# SchedaRobotica.net
KiCad netlist of a schematic drawn in EAGLE
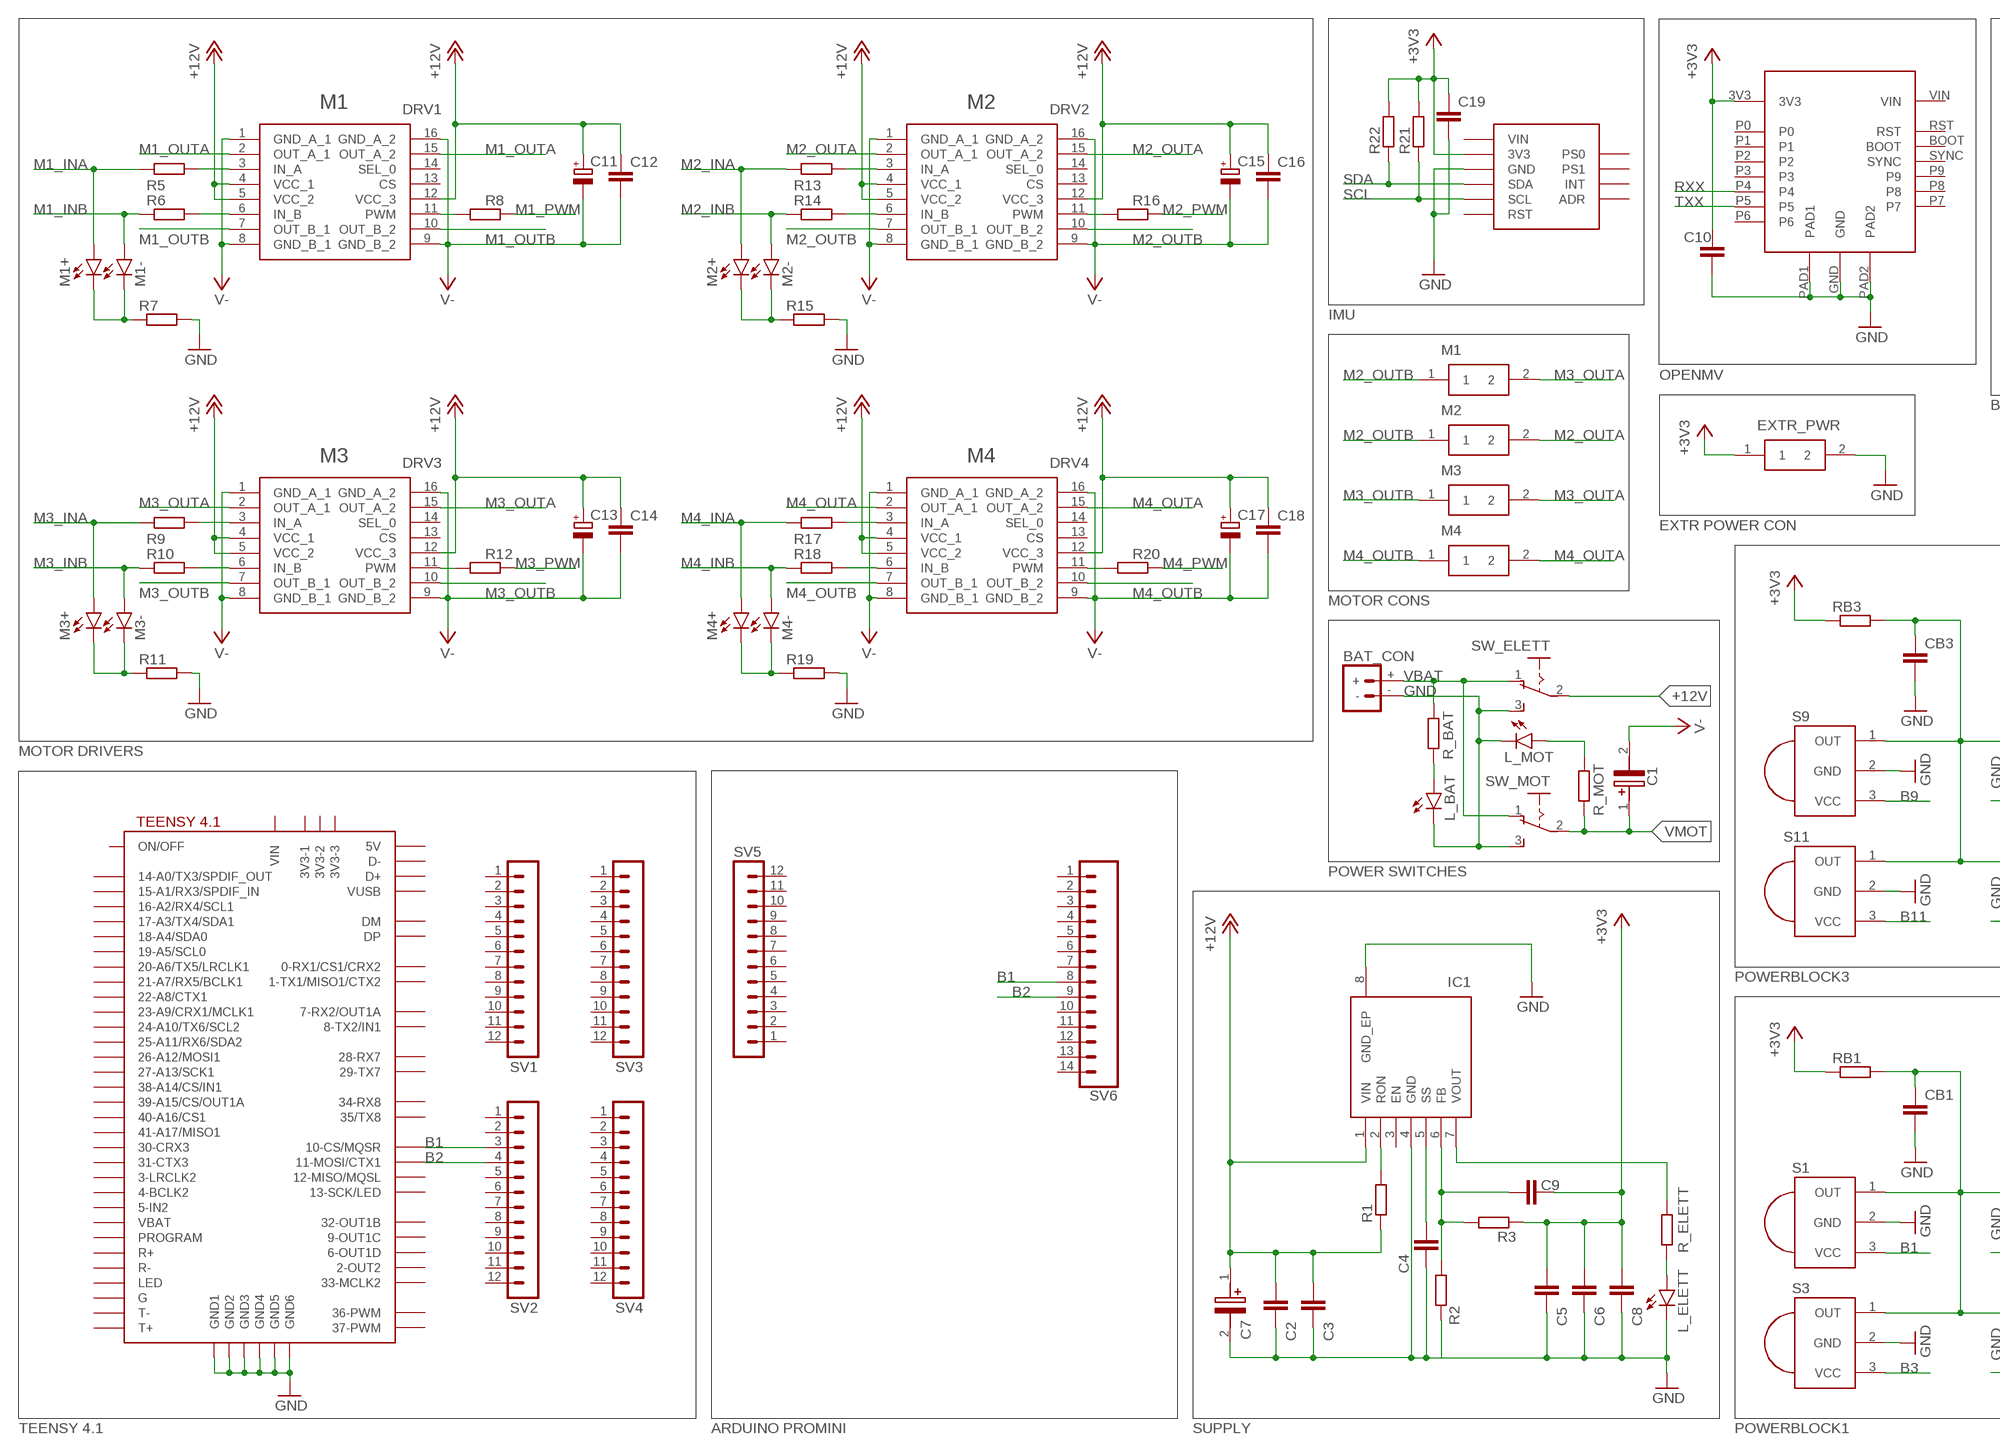
[diagram p0: schematic, sheet 1, part 1 of 2]
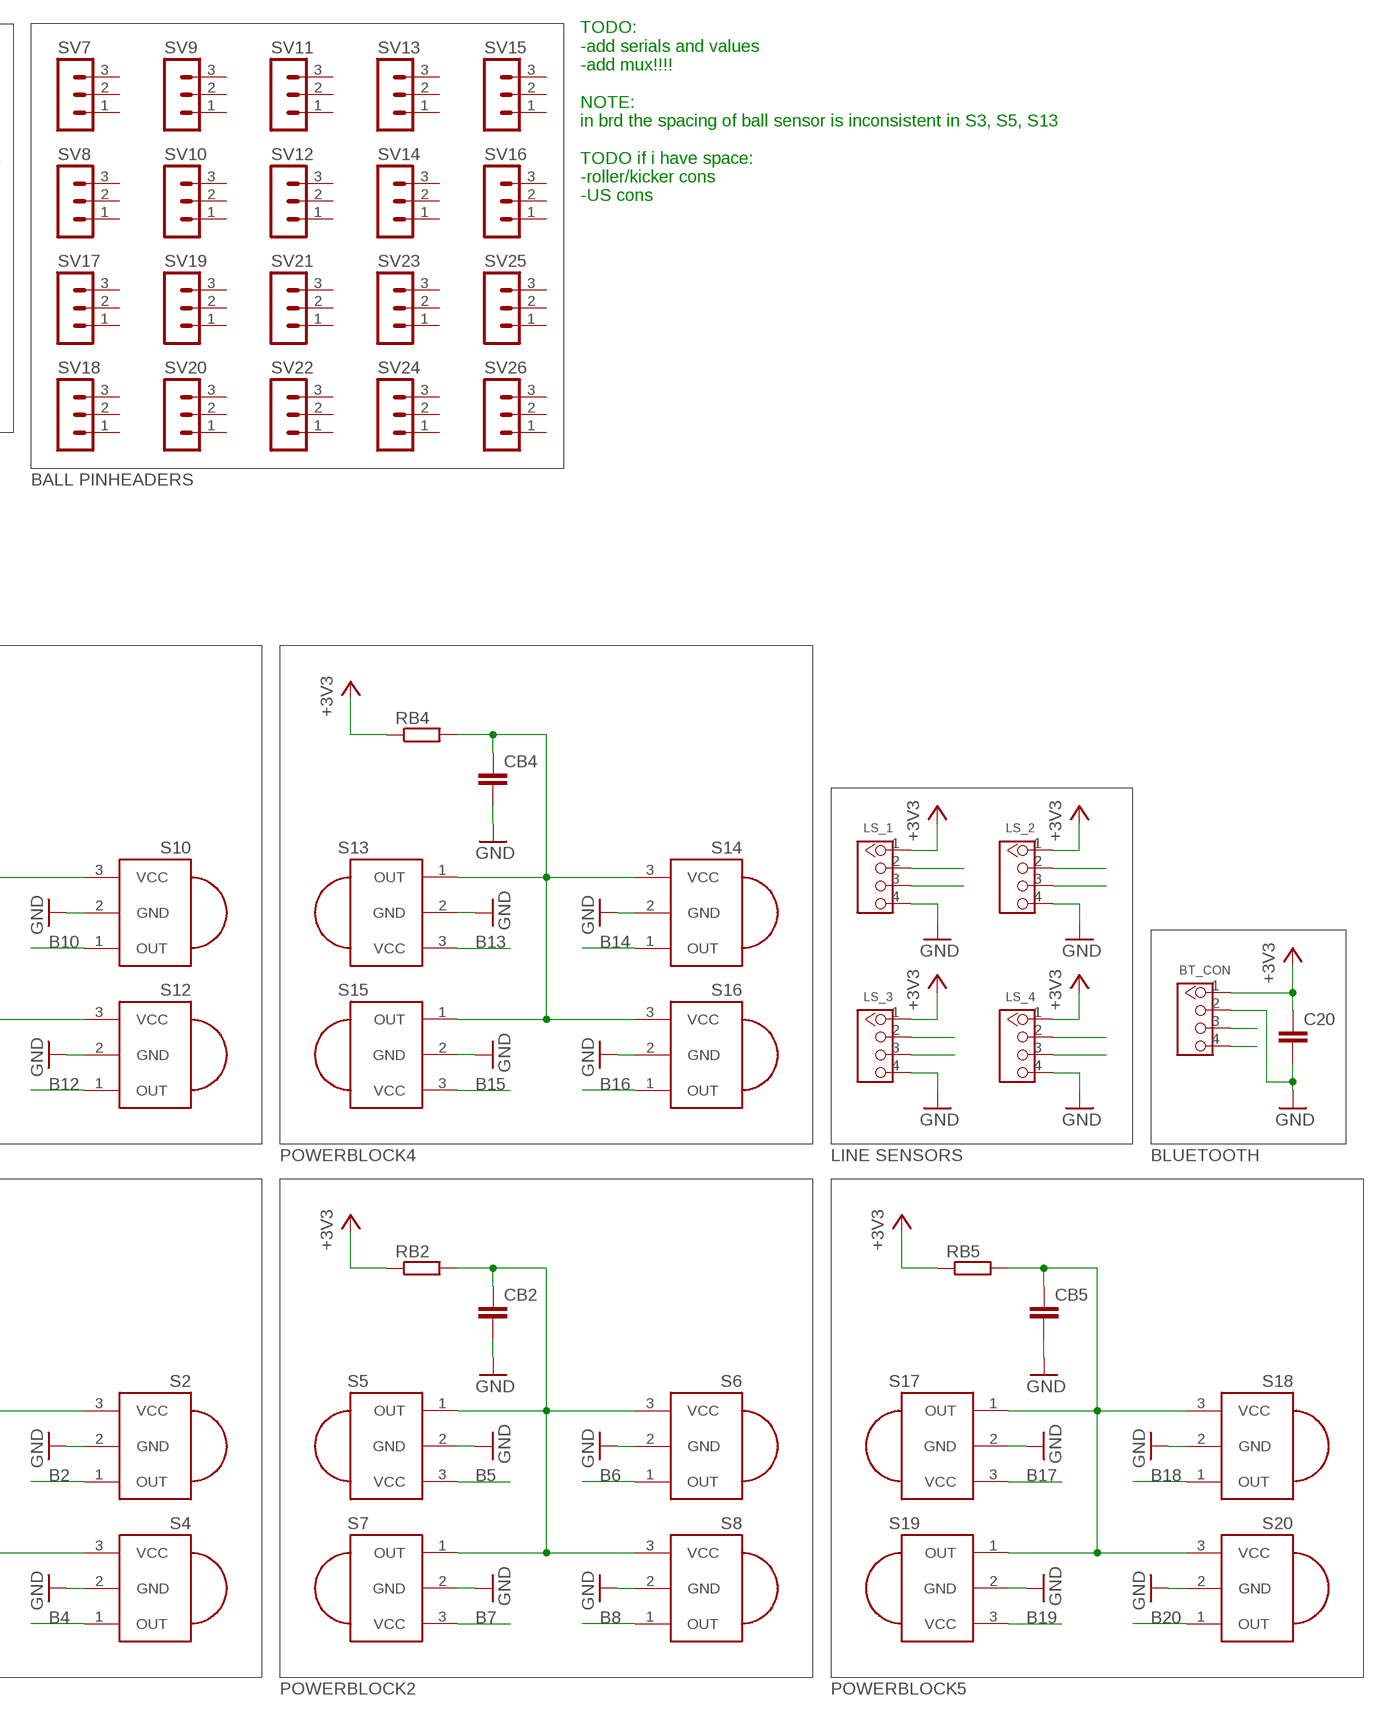
[diagram p1: schematic, sheet 1, part 2 of 2]

(export (version "E")
  (design (tool "Eeschema 10.0.6"))
  (components
    (comp (ref "BAT_CON")
      (value "BATTERY_CONN_DEANS")
      (footprint "eagle-import:DEANS")
      (libsource (lib "eagle-import") (part "BATTERY_CONN_DEANS"))
    )
    (comp (ref "BT_CON")
      (value "4P-2.0")
      (footprint "eagle-import:HW4-2.0")
      (libsource (lib "eagle-import") (part "GROVE-CONNECTOR-DIP(4P-2.0)"))
    )
    (comp (ref "C1")
      (value "EEV-FK1C152Q")
      (footprint "eagle-import:FKV(H13)")
      (fields (field (name "MOUSER_PART_NUMBER") "667-EEV-FK1C152Q"))
      (libsource (lib "eagle-import") (part "EEV-FK1C152Q"))
    )
    (comp (ref "C2")
      (value "100n")
      (footprint "eagle-import:C0805")
      (libsource (lib "eagle-import") (part "C-EUC0805"))
    )
    (comp (ref "C3")
      (value "100n")
      (footprint "eagle-import:C0805")
      (libsource (lib "eagle-import") (part "C-EUC0805"))
    )
    (comp (ref "C4")
      (value "22n")
      (footprint "eagle-import:C0805")
      (libsource (lib "eagle-import") (part "C-EUC0805"))
    )
    (comp (ref "C5")
      (value "100u")
      (footprint "eagle-import:C1206")
      (libsource (lib "eagle-import") (part "C-EUC1206"))
    )
    (comp (ref "C6")
      (value "100u")
      (footprint "eagle-import:C1206")
      (libsource (lib "eagle-import") (part "C-EUC1206"))
    )
    (comp (ref "C7")
      (value "EEV-FK1C152Q")
      (footprint "eagle-import:FKV(H13)")
      (fields (field (name "MOUSER_PART_NUMBER") "667-EEV-FK1C152Q"))
      (libsource (lib "eagle-import") (part "EEV-FK1C152Q"))
    )
    (comp (ref "C8")
      (value "100n")
      (footprint "eagle-import:C0805")
      (libsource (lib "eagle-import") (part "C-EUC0805"))
    )
    (comp (ref "C9")
      (value "22n")
      (footprint "eagle-import:C0805")
      (libsource (lib "eagle-import") (part "C-EUC0805"))
    )
    (comp (ref "C10")
      (value "100u")
      (footprint "eagle-import:C1206")
      (libsource (lib "eagle-import") (part "C-EUC1206"))
    )
    (comp (ref "C11")
      (value "CPOL-EUE")
      (footprint "eagle-import:PANASONIC_E")
      (libsource (lib "eagle-import") (part "CPOL-EUE"))
    )
    (comp (ref "C12")
      (value "C-EUC0805")
      (footprint "eagle-import:C0805")
      (libsource (lib "eagle-import") (part "C-EUC0805"))
    )
    (comp (ref "C13")
      (value "CPOL-EUE")
      (footprint "eagle-import:PANASONIC_E")
      (libsource (lib "eagle-import") (part "CPOL-EUE"))
    )
    (comp (ref "C14")
      (value "C-EUC0805")
      (footprint "eagle-import:C0805")
      (libsource (lib "eagle-import") (part "C-EUC0805"))
    )
    (comp (ref "C15")
      (value "CPOL-EUE")
      (footprint "eagle-import:PANASONIC_E")
      (libsource (lib "eagle-import") (part "CPOL-EUE"))
    )
    (comp (ref "C16")
      (value "C-EUC0805")
      (footprint "eagle-import:C0805")
      (libsource (lib "eagle-import") (part "C-EUC0805"))
    )
    (comp (ref "C17")
      (value "CPOL-EUE")
      (footprint "eagle-import:PANASONIC_E")
      (libsource (lib "eagle-import") (part "CPOL-EUE"))
    )
    (comp (ref "C18")
      (value "C-EUC0805")
      (footprint "eagle-import:C0805")
      (libsource (lib "eagle-import") (part "C-EUC0805"))
    )
    (comp (ref "C19")
      (value "1u")
      (footprint "eagle-import:C0805")
      (libsource (lib "eagle-import") (part "C-EUC0805"))
    )
    (comp (ref "C20")
      (value "1u")
      (footprint "eagle-import:C0805")
      (libsource (lib "eagle-import") (part "C-EUC0805"))
    )
    (comp (ref "CB1")
      (value "C-EUC0805")
      (footprint "eagle-import:C0805")
      (libsource (lib "eagle-import") (part "C-EUC0805"))
    )
    (comp (ref "CB2")
      (value "C-EUC0805")
      (footprint "eagle-import:C0805")
      (libsource (lib "eagle-import") (part "C-EUC0805"))
    )
    (comp (ref "CB3")
      (value "C-EUC0805")
      (footprint "eagle-import:C0805")
      (libsource (lib "eagle-import") (part "C-EUC0805"))
    )
    (comp (ref "CB4")
      (value "C-EUC0805")
      (footprint "eagle-import:C0805")
      (libsource (lib "eagle-import") (part "C-EUC0805"))
    )
    (comp (ref "CB5")
      (value "C-EUC0805")
      (footprint "eagle-import:C0805")
      (libsource (lib "eagle-import") (part "C-EUC0805"))
    )
    (comp (ref "DRV1")
      (value "VNH7070ASTR")
      (footprint "eagle-import:SOIC127P600X175-16N")
      (fields
        (field (name "MOUSER_PART_NUMBER") "511-VNH7070ASTR")
        (field (name "RS_PART_NUMBER") "1647017P")
      )
      (libsource (lib "eagle-import") (part "VNH7070ASTR"))
    )
    (comp (ref "DRV2")
      (value "VNH7070ASTR")
      (footprint "eagle-import:SOIC127P600X175-16N")
      (fields
        (field (name "MOUSER_PART_NUMBER") "511-VNH7070ASTR")
        (field (name "RS_PART_NUMBER") "1647017P")
      )
      (libsource (lib "eagle-import") (part "VNH7070ASTR"))
    )
    (comp (ref "DRV3")
      (value "VNH7070ASTR")
      (footprint "eagle-import:SOIC127P600X175-16N")
      (fields
        (field (name "MOUSER_PART_NUMBER") "511-VNH7070ASTR")
        (field (name "RS_PART_NUMBER") "1647017P")
      )
      (libsource (lib "eagle-import") (part "VNH7070ASTR"))
    )
    (comp (ref "DRV4")
      (value "VNH7070ASTR")
      (footprint "eagle-import:SOIC127P600X175-16N")
      (fields
        (field (name "MOUSER_PART_NUMBER") "511-VNH7070ASTR")
        (field (name "RS_PART_NUMBER") "1647017P")
      )
      (libsource (lib "eagle-import") (part "VNH7070ASTR"))
    )
    (comp (ref "EXTR_PWR")
      (value "43650-0201")
      (footprint "eagle-import:43650-0200")
      (fields (field (name "MOUSER_PART_NUMBER") "538-43650-0201"))
      (libsource (lib "eagle-import") (part "43650-0201"))
    )
    (comp (ref "IC1")
      (value "LMZ14202TZE-ADJ_NOPB")
      (footprint "eagle-import:NDW0007A")
      (fields
        (field (name "MANUFACTURER_PART_NUMBER") "LMZ14202TZE-ADJ/NOPB")
        (field (name "MOUSER_PART_NUMBER") "926-LM14202TZEADJNPB")
        (field (name "RS_PART_NUMBER") "7981195P")
      )
      (libsource (lib "eagle-import") (part "LMZ14202TZE-ADJ_NOPB"))
    )
    (comp (ref "LS_1")
      (value "4P-2.0")
      (footprint "eagle-import:HW4-2.0")
      (libsource (lib "eagle-import") (part "GROVE-CONNECTOR-DIP(4P-2.0)"))
    )
    (comp (ref "LS_2")
      (value "4P-2.0")
      (footprint "eagle-import:HW4-2.0")
      (libsource (lib "eagle-import") (part "GROVE-CONNECTOR-DIP(4P-2.0)"))
    )
    (comp (ref "LS_3")
      (value "4P-2.0")
      (footprint "eagle-import:HW4-2.0")
      (libsource (lib "eagle-import") (part "GROVE-CONNECTOR-DIP(4P-2.0)"))
    )
    (comp (ref "LS_4")
      (value "4P-2.0")
      (footprint "eagle-import:HW4-2.0")
      (libsource (lib "eagle-import") (part "GROVE-CONNECTOR-DIP(4P-2.0)"))
    )
    (comp (ref "L_BAT")
      (value "LEDCHIPLED_1206")
      (footprint "eagle-import:CHIPLED_1206")
      (libsource (lib "eagle-import") (part "LEDCHIPLED_1206"))
    )
    (comp (ref "L_ELETT")
      (value "LEDCHIPLED_1206")
      (footprint "eagle-import:CHIPLED_1206")
      (libsource (lib "eagle-import") (part "LEDCHIPLED_1206"))
    )
    (comp (ref "L_MOT")
      (value "LEDCHIPLED_1206")
      (footprint "eagle-import:CHIPLED_1206")
      (libsource (lib "eagle-import") (part "LEDCHIPLED_1206"))
    )
    (comp (ref "M1")
      (value "43650-0201")
      (footprint "eagle-import:43650-0200")
      (fields (field (name "MOUSER_PART_NUMBER") "538-43650-0201"))
      (libsource (lib "eagle-import") (part "43650-0201"))
    )
    (comp (ref "M1+")
      (value "LEDCHIPLED_1206")
      (footprint "eagle-import:CHIPLED_1206")
      (libsource (lib "eagle-import") (part "LEDCHIPLED_1206"))
    )
    (comp (ref "M1-")
      (value "LEDCHIPLED_1206")
      (footprint "eagle-import:CHIPLED_1206")
      (libsource (lib "eagle-import") (part "LEDCHIPLED_1206"))
    )
    (comp (ref "M2")
      (value "43650-0201")
      (footprint "eagle-import:43650-0200")
      (fields (field (name "MOUSER_PART_NUMBER") "538-43650-0201"))
      (libsource (lib "eagle-import") (part "43650-0201"))
    )
    (comp (ref "M2+")
      (value "LEDCHIPLED_1206")
      (footprint "eagle-import:CHIPLED_1206")
      (libsource (lib "eagle-import") (part "LEDCHIPLED_1206"))
    )
    (comp (ref "M2-")
      (value "LEDCHIPLED_1206")
      (footprint "eagle-import:CHIPLED_1206")
      (libsource (lib "eagle-import") (part "LEDCHIPLED_1206"))
    )
    (comp (ref "M3")
      (value "43650-0201")
      (footprint "eagle-import:43650-0200")
      (fields (field (name "MOUSER_PART_NUMBER") "538-43650-0201"))
      (libsource (lib "eagle-import") (part "43650-0201"))
    )
    (comp (ref "M3+")
      (value "LEDCHIPLED_1206")
      (footprint "eagle-import:CHIPLED_1206")
      (libsource (lib "eagle-import") (part "LEDCHIPLED_1206"))
    )
    (comp (ref "M3-")
      (value "LEDCHIPLED_1206")
      (footprint "eagle-import:CHIPLED_1206")
      (libsource (lib "eagle-import") (part "LEDCHIPLED_1206"))
    )
    (comp (ref "M4")
      (value "43650-0201")
      (footprint "eagle-import:43650-0200")
      (fields (field (name "MOUSER_PART_NUMBER") "538-43650-0201"))
      (libsource (lib "eagle-import") (part "43650-0201"))
    )
    (comp (ref "M4+")
      (value "LEDCHIPLED_1206")
      (footprint "eagle-import:CHIPLED_1206")
      (libsource (lib "eagle-import") (part "LEDCHIPLED_1206"))
    )
    (comp (ref "M4-")
      (value "LEDCHIPLED_1206")
      (footprint "eagle-import:CHIPLED_1206")
      (libsource (lib "eagle-import") (part "LEDCHIPLED_1206"))
    )
    (comp (ref "R1")
      (value "61,9k")
      (footprint "eagle-import:M0805")
      (libsource (lib "eagle-import") (part "R-EU_M0805"))
    )
    (comp (ref "R2")
      (value "1,07k")
      (footprint "eagle-import:M0805")
      (libsource (lib "eagle-import") (part "R-EU_M0805"))
    )
    (comp (ref "R3")
      (value "3,32k")
      (footprint "eagle-import:M0805")
      (libsource (lib "eagle-import") (part "R-EU_M0805"))
    )
    (comp (ref "R5")
      (value "R-EU_M0805")
      (footprint "eagle-import:M0805")
      (libsource (lib "eagle-import") (part "R-EU_M0805"))
    )
    (comp (ref "R6")
      (value "R-EU_M0805")
      (footprint "eagle-import:M0805")
      (libsource (lib "eagle-import") (part "R-EU_M0805"))
    )
    (comp (ref "R7")
      (value "R-EU_M0805")
      (footprint "eagle-import:M0805")
      (libsource (lib "eagle-import") (part "R-EU_M0805"))
    )
    (comp (ref "R8")
      (value "R-EU_M0805")
      (footprint "eagle-import:M0805")
      (libsource (lib "eagle-import") (part "R-EU_M0805"))
    )
    (comp (ref "R9")
      (value "R-EU_M0805")
      (footprint "eagle-import:M0805")
      (libsource (lib "eagle-import") (part "R-EU_M0805"))
    )
    (comp (ref "R10")
      (value "R-EU_M0805")
      (footprint "eagle-import:M0805")
      (libsource (lib "eagle-import") (part "R-EU_M0805"))
    )
    (comp (ref "R11")
      (value "R-EU_M0805")
      (footprint "eagle-import:M0805")
      (libsource (lib "eagle-import") (part "R-EU_M0805"))
    )
    (comp (ref "R12")
      (value "R-EU_M0805")
      (footprint "eagle-import:M0805")
      (libsource (lib "eagle-import") (part "R-EU_M0805"))
    )
    (comp (ref "R13")
      (value "R-EU_M0805")
      (footprint "eagle-import:M0805")
      (libsource (lib "eagle-import") (part "R-EU_M0805"))
    )
    (comp (ref "R14")
      (value "R-EU_M0805")
      (footprint "eagle-import:M0805")
      (libsource (lib "eagle-import") (part "R-EU_M0805"))
    )
    (comp (ref "R15")
      (value "R-EU_M0805")
      (footprint "eagle-import:M0805")
      (libsource (lib "eagle-import") (part "R-EU_M0805"))
    )
    (comp (ref "R16")
      (value "R-EU_M0805")
      (footprint "eagle-import:M0805")
      (libsource (lib "eagle-import") (part "R-EU_M0805"))
    )
    (comp (ref "R17")
      (value "R-EU_M0805")
      (footprint "eagle-import:M0805")
      (libsource (lib "eagle-import") (part "R-EU_M0805"))
    )
    (comp (ref "R18")
      (value "R-EU_M0805")
      (footprint "eagle-import:M0805")
      (libsource (lib "eagle-import") (part "R-EU_M0805"))
    )
    (comp (ref "R19")
      (value "R-EU_M0805")
      (footprint "eagle-import:M0805")
      (libsource (lib "eagle-import") (part "R-EU_M0805"))
    )
    (comp (ref "R20")
      (value "R-EU_M0805")
      (footprint "eagle-import:M0805")
      (libsource (lib "eagle-import") (part "R-EU_M0805"))
    )
    (comp (ref "R21")
      (value "10k")
      (footprint "eagle-import:M0805")
      (libsource (lib "eagle-import") (part "R-EU_M0805"))
    )
    (comp (ref "R22")
      (value "10k")
      (footprint "eagle-import:M0805")
      (libsource (lib "eagle-import") (part "R-EU_M0805"))
    )
    (comp (ref "RB1")
      (value "R-EU_M0805")
      (footprint "eagle-import:M0805")
      (libsource (lib "eagle-import") (part "R-EU_M0805"))
    )
    (comp (ref "RB2")
      (value "R-EU_M0805")
      (footprint "eagle-import:M0805")
      (libsource (lib "eagle-import") (part "R-EU_M0805"))
    )
    (comp (ref "RB3")
      (value "R-EU_M0805")
      (footprint "eagle-import:M0805")
      (libsource (lib "eagle-import") (part "R-EU_M0805"))
    )
    (comp (ref "RB4")
      (value "R-EU_M0805")
      (footprint "eagle-import:M0805")
      (libsource (lib "eagle-import") (part "R-EU_M0805"))
    )
    (comp (ref "RB5")
      (value "R-EU_M0805")
      (footprint "eagle-import:M0805")
      (libsource (lib "eagle-import") (part "R-EU_M0805"))
    )
    (comp (ref "R_BAT")
      (value "R-EU_M0805")
      (footprint "eagle-import:M0805")
      (libsource (lib "eagle-import") (part "R-EU_M0805"))
    )
    (comp (ref "R_ELETT")
      (value "R-EU_M0805")
      (footprint "eagle-import:M0805")
      (libsource (lib "eagle-import") (part "R-EU_M0805"))
    )
    (comp (ref "R_MOT")
      (value "R-EU_M0805")
      (footprint "eagle-import:M0805")
      (libsource (lib "eagle-import") (part "R-EU_M0805"))
    )
    (comp (ref "S1")
      (value "PNA460XM")
      (footprint "eagle-import:PNA460XM")
      (libsource (lib "eagle-import") (part "PNA460XM"))
    )
    (comp (ref "S2")
      (value "PNA460XM")
      (footprint "eagle-import:PNA460XM")
      (libsource (lib "eagle-import") (part "PNA460XM"))
    )
    (comp (ref "S3")
      (value "PNA460XM")
      (footprint "eagle-import:PNA460XM")
      (libsource (lib "eagle-import") (part "PNA460XM"))
    )
    (comp (ref "S4")
      (value "PNA460XM")
      (footprint "eagle-import:PNA460XM")
      (libsource (lib "eagle-import") (part "PNA460XM"))
    )
    (comp (ref "S5")
      (value "PNA460XM")
      (footprint "eagle-import:PNA460XM")
      (libsource (lib "eagle-import") (part "PNA460XM"))
    )
    (comp (ref "S6")
      (value "PNA460XM")
      (footprint "eagle-import:PNA460XM")
      (libsource (lib "eagle-import") (part "PNA460XM"))
    )
    (comp (ref "S7")
      (value "PNA460XM")
      (footprint "eagle-import:PNA460XM")
      (libsource (lib "eagle-import") (part "PNA460XM"))
    )
    (comp (ref "S8")
      (value "PNA460XM")
      (footprint "eagle-import:PNA460XM")
      (libsource (lib "eagle-import") (part "PNA460XM"))
    )
    (comp (ref "S9")
      (value "PNA460XM")
      (footprint "eagle-import:PNA460XM")
      (libsource (lib "eagle-import") (part "PNA460XM"))
    )
    (comp (ref "S10")
      (value "PNA460XM")
      (footprint "eagle-import:PNA460XM")
      (libsource (lib "eagle-import") (part "PNA460XM"))
    )
    (comp (ref "S11")
      (value "PNA460XM")
      (footprint "eagle-import:PNA460XM")
      (libsource (lib "eagle-import") (part "PNA460XM"))
    )
    (comp (ref "S12")
      (value "PNA460XM")
      (footprint "eagle-import:PNA460XM")
      (libsource (lib "eagle-import") (part "PNA460XM"))
    )
    (comp (ref "S13")
      (value "PNA460XM")
      (footprint "eagle-import:PNA460XM")
      (libsource (lib "eagle-import") (part "PNA460XM"))
    )
    (comp (ref "S14")
      (value "PNA460XM")
      (footprint "eagle-import:PNA460XM")
      (libsource (lib "eagle-import") (part "PNA460XM"))
    )
    (comp (ref "S15")
      (value "PNA460XM")
      (footprint "eagle-import:PNA460XM")
      (libsource (lib "eagle-import") (part "PNA460XM"))
    )
    (comp (ref "S16")
      (value "PNA460XM")
      (footprint "eagle-import:PNA460XM")
      (libsource (lib "eagle-import") (part "PNA460XM"))
    )
    (comp (ref "S17")
      (value "PNA460XM")
      (footprint "eagle-import:PNA460XM")
      (libsource (lib "eagle-import") (part "PNA460XM"))
    )
    (comp (ref "S18")
      (value "PNA460XM")
      (footprint "eagle-import:PNA460XM")
      (libsource (lib "eagle-import") (part "PNA460XM"))
    )
    (comp (ref "S19")
      (value "PNA460XM")
      (footprint "eagle-import:PNA460XM")
      (libsource (lib "eagle-import") (part "PNA460XM"))
    )
    (comp (ref "S20")
      (value "PNA460XM")
      (footprint "eagle-import:PNA460XM")
      (libsource (lib "eagle-import") (part "PNA460XM"))
    )
    (comp (ref "SV1")
      (value "MA12-1")
      (footprint "eagle-import:MA12-1")
      (libsource (lib "eagle-import") (part "MA12-1"))
    )
    (comp (ref "SV2")
      (value "MA12-1")
      (footprint "eagle-import:MA12-1")
      (libsource (lib "eagle-import") (part "MA12-1"))
    )
    (comp (ref "SV3")
      (value "MA12-1")
      (footprint "eagle-import:MA12-1")
      (libsource (lib "eagle-import") (part "MA12-1"))
    )
    (comp (ref "SV4")
      (value "MA12-1")
      (footprint "eagle-import:MA12-1")
      (libsource (lib "eagle-import") (part "MA12-1"))
    )
    (comp (ref "SV5")
      (value "MA12-1")
      (footprint "eagle-import:MA12-1")
      (libsource (lib "eagle-import") (part "MA12-1"))
    )
    (comp (ref "SV6")
      (value "CONN_14LONGPADS")
      (footprint "eagle-import:1X14-LONGPADS")
      (libsource (lib "eagle-import") (part "CONN_14LONGPADS"))
    )
    (comp (ref "SV7")
      (value "MA03-1")
      (footprint "eagle-import:MA03-1")
      (libsource (lib "eagle-import") (part "MA03-1"))
    )
    (comp (ref "SV8")
      (value "MA03-1")
      (footprint "eagle-import:MA03-1")
      (libsource (lib "eagle-import") (part "MA03-1"))
    )
    (comp (ref "SV9")
      (value "MA03-1")
      (footprint "eagle-import:MA03-1")
      (libsource (lib "eagle-import") (part "MA03-1"))
    )
    (comp (ref "SV10")
      (value "MA03-1")
      (footprint "eagle-import:MA03-1")
      (libsource (lib "eagle-import") (part "MA03-1"))
    )
    (comp (ref "SV11")
      (value "MA03-1")
      (footprint "eagle-import:MA03-1")
      (libsource (lib "eagle-import") (part "MA03-1"))
    )
    (comp (ref "SV12")
      (value "MA03-1")
      (footprint "eagle-import:MA03-1")
      (libsource (lib "eagle-import") (part "MA03-1"))
    )
    (comp (ref "SV13")
      (value "MA03-1")
      (footprint "eagle-import:MA03-1")
      (libsource (lib "eagle-import") (part "MA03-1"))
    )
    (comp (ref "SV14")
      (value "MA03-1")
      (footprint "eagle-import:MA03-1")
      (libsource (lib "eagle-import") (part "MA03-1"))
    )
    (comp (ref "SV15")
      (value "MA03-1")
      (footprint "eagle-import:MA03-1")
      (libsource (lib "eagle-import") (part "MA03-1"))
    )
    (comp (ref "SV16")
      (value "MA03-1")
      (footprint "eagle-import:MA03-1")
      (libsource (lib "eagle-import") (part "MA03-1"))
    )
    (comp (ref "SV17")
      (value "MA03-1")
      (footprint "eagle-import:MA03-1")
      (libsource (lib "eagle-import") (part "MA03-1"))
    )
    (comp (ref "SV18")
      (value "MA03-1")
      (footprint "eagle-import:MA03-1")
      (libsource (lib "eagle-import") (part "MA03-1"))
    )
    (comp (ref "SV19")
      (value "MA03-1")
      (footprint "eagle-import:MA03-1")
      (libsource (lib "eagle-import") (part "MA03-1"))
    )
    (comp (ref "SV20")
      (value "MA03-1")
      (footprint "eagle-import:MA03-1")
      (libsource (lib "eagle-import") (part "MA03-1"))
    )
    (comp (ref "SV21")
      (value "MA03-1")
      (footprint "eagle-import:MA03-1")
      (libsource (lib "eagle-import") (part "MA03-1"))
    )
    (comp (ref "SV22")
      (value "MA03-1")
      (footprint "eagle-import:MA03-1")
      (libsource (lib "eagle-import") (part "MA03-1"))
    )
    (comp (ref "SV23")
      (value "MA03-1")
      (footprint "eagle-import:MA03-1")
      (libsource (lib "eagle-import") (part "MA03-1"))
    )
    (comp (ref "SV24")
      (value "MA03-1")
      (footprint "eagle-import:MA03-1")
      (libsource (lib "eagle-import") (part "MA03-1"))
    )
    (comp (ref "SV25")
      (value "MA03-1")
      (footprint "eagle-import:MA03-1")
      (libsource (lib "eagle-import") (part "MA03-1"))
    )
    (comp (ref "SV26")
      (value "MA03-1")
      (footprint "eagle-import:MA03-1")
      (libsource (lib "eagle-import") (part "MA03-1"))
    )
    (comp (ref "SW_ELETT")
      (value "255SB")
      (footprint "eagle-import:255SB")
      (libsource (lib "eagle-import") (part "255SB"))
    )
    (comp (ref "SW_MOT")
      (value "255SB")
      (footprint "eagle-import:255SB")
      (libsource (lib "eagle-import") (part "255SB"))
    )
    (comp (ref "U$1")
      (value "TEENSY41")
      (footprint "eagle-import:TEENSY41")
      (libsource (lib "eagle-import") (part "TEENSY41"))
    )
    (comp (ref "U$2")
      (value "OPENMV_H7")
      (footprint "eagle-import:OPENMV_H7")
      (libsource (lib "eagle-import") (part "OPENMV_H7"))
    )
    (comp (ref "U$3")
      (value "BNO055_BNO055")
      (footprint "eagle-import:BNO055_BNO055")
      (libsource (lib "eagle-import") (part "BNO055_BNO055"))
    )
  )
  (nets
    (net (code "1") (name "+3V3") (class "Default")
      (node (ref "BT_CON") (pin "1") (pinfunction "1_1") (pintype "bidirectional"))
      (node (ref "C10") (pin "1") (pinfunction "1_1") (pintype "passive"))
      (node (ref "C19") (pin "1") (pinfunction "1_1") (pintype "passive"))
      (node (ref "C20") (pin "1") (pinfunction "1_1") (pintype "passive"))
      (node (ref "C5") (pin "1") (pinfunction "1_1") (pintype "passive"))
      (node (ref "C6") (pin "1") (pinfunction "1_1") (pintype "passive"))
      (node (ref "C8") (pin "1") (pinfunction "1_1") (pintype "passive"))
      (node (ref "C9") (pin "2") (pinfunction "2_2") (pintype "passive"))
      (node (ref "EXTR_PWR") (pin "1") (pinfunction "1_1") (pintype "bidirectional"))
      (node (ref "LS_1") (pin "1") (pinfunction "1_1") (pintype "bidirectional"))
      (node (ref "LS_2") (pin "1") (pinfunction "1_1") (pintype "bidirectional"))
      (node (ref "LS_3") (pin "1") (pinfunction "1_1") (pintype "bidirectional"))
      (node (ref "LS_4") (pin "1") (pinfunction "1_1") (pintype "bidirectional"))
      (node (ref "R21") (pin "2") (pinfunction "2_2") (pintype "passive"))
      (node (ref "R22") (pin "2") (pinfunction "2_2") (pintype "passive"))
      (node (ref "R3") (pin "1") (pinfunction "1_1") (pintype "passive"))
      (node (ref "RB1") (pin "1") (pinfunction "1_1") (pintype "passive"))
      (node (ref "RB2") (pin "1") (pinfunction "1_1") (pintype "passive"))
      (node (ref "RB3") (pin "1") (pinfunction "1_1") (pintype "passive"))
      (node (ref "RB4") (pin "1") (pinfunction "1_1") (pintype "passive"))
      (node (ref "RB5") (pin "1") (pinfunction "1_1") (pintype "passive"))
      (node (ref "U$2") (pin "3V3") (pinfunction "3V3_3V3") (pintype "bidirectional"))
      (node (ref "U$3") (pin "3V3") (pinfunction "3V3_3V3") (pintype "bidirectional"))
    )
    (net (code "2") (name "+12V") (class "Default")
      (node (ref "C11") (pin "+") (pinfunction "+_+") (pintype "passive"))
      (node (ref "C12") (pin "1") (pinfunction "1_1") (pintype "passive"))
      (node (ref "C13") (pin "+") (pinfunction "+_+") (pintype "passive"))
      (node (ref "C14") (pin "1") (pinfunction "1_1") (pintype "passive"))
      (node (ref "C15") (pin "+") (pinfunction "+_+") (pintype "passive"))
      (node (ref "C16") (pin "1") (pinfunction "1_1") (pintype "passive"))
      (node (ref "C17") (pin "+") (pinfunction "+_+") (pintype "passive"))
      (node (ref "C18") (pin "1") (pinfunction "1_1") (pintype "passive"))
      (node (ref "C2") (pin "1") (pinfunction "1_1") (pintype "passive"))
      (node (ref "C3") (pin "1") (pinfunction "1_1") (pintype "passive"))
      (node (ref "C7") (pin "1") (pinfunction "+_1") (pintype "bidirectional"))
      (node (ref "DRV1") (pin "12") (pinfunction "VCC_3_12") (pintype "bidirectional"))
      (node (ref "DRV1") (pin "4") (pinfunction "VCC_1_4") (pintype "bidirectional"))
      (node (ref "DRV1") (pin "5") (pinfunction "VCC_2_5") (pintype "bidirectional"))
      (node (ref "DRV2") (pin "12") (pinfunction "VCC_3_12") (pintype "bidirectional"))
      (node (ref "DRV2") (pin "4") (pinfunction "VCC_1_4") (pintype "bidirectional"))
      (node (ref "DRV2") (pin "5") (pinfunction "VCC_2_5") (pintype "bidirectional"))
      (node (ref "DRV3") (pin "12") (pinfunction "VCC_3_12") (pintype "bidirectional"))
      (node (ref "DRV3") (pin "4") (pinfunction "VCC_1_4") (pintype "bidirectional"))
      (node (ref "DRV3") (pin "5") (pinfunction "VCC_2_5") (pintype "bidirectional"))
      (node (ref "DRV4") (pin "12") (pinfunction "VCC_3_12") (pintype "bidirectional"))
      (node (ref "DRV4") (pin "4") (pinfunction "VCC_1_4") (pintype "bidirectional"))
      (node (ref "DRV4") (pin "5") (pinfunction "VCC_2_5") (pintype "bidirectional"))
      (node (ref "IC1") (pin "1") (pinfunction "VIN_1") (pintype "input"))
      (node (ref "R1") (pin "1") (pinfunction "1_1") (pintype "passive"))
      (node (ref "SW_ELETT") (pin "2") (pinfunction "P_2") (pintype "passive"))
    )
    (net (code "3") (name "/B1") (class "Default")
      (node (ref "S1") (pin "3") (pinfunction "VCC_3") (pintype "power_in"))
      (node (ref "SV2") (pin "3") (pinfunction "3_3") (pintype "passive"))
      (node (ref "SV6") (pin "8") (pinfunction "8_8") (pintype "passive"))
      (node (ref "U$1") (pin "10-CS\\MQSR") (pinfunction "10-CS/MQSR_10-CS\\MQSR") (pintype "bidirectional"))
    )
    (net (code "4") (name "/B2") (class "Default")
      (node (ref "S2") (pin "1") (pinfunction "OUT_1") (pintype "output"))
      (node (ref "SV2") (pin "4") (pinfunction "4_4") (pintype "passive"))
      (node (ref "SV6") (pin "9") (pinfunction "9_9") (pintype "passive"))
      (node (ref "U$1") (pin "11-MOSI/CTX1") (pinfunction "11-MOSI/CTX1_11-MOSI/CTX1") (pintype "bidirectional"))
    )
    (net (code "5") (name "/B3") (class "Default")
      (node (ref "S3") (pin "3") (pinfunction "VCC_3") (pintype "power_in"))
    )
    (net (code "6") (name "/B4") (class "Default")
      (node (ref "S4") (pin "1") (pinfunction "OUT_1") (pintype "output"))
    )
    (net (code "7") (name "/B5") (class "Default")
      (node (ref "S5") (pin "3") (pinfunction "VCC_3") (pintype "power_in"))
    )
    (net (code "8") (name "/B6") (class "Default")
      (node (ref "S6") (pin "1") (pinfunction "OUT_1") (pintype "output"))
    )
    (net (code "9") (name "/B7") (class "Default")
      (node (ref "S7") (pin "3") (pinfunction "VCC_3") (pintype "power_in"))
    )
    (net (code "10") (name "/B8") (class "Default")
      (node (ref "S8") (pin "1") (pinfunction "OUT_1") (pintype "output"))
    )
    (net (code "11") (name "/B9") (class "Default")
      (node (ref "S9") (pin "3") (pinfunction "VCC_3") (pintype "power_in"))
    )
    (net (code "12") (name "/B10") (class "Default")
      (node (ref "S10") (pin "1") (pinfunction "OUT_1") (pintype "output"))
    )
    (net (code "13") (name "/B11") (class "Default")
      (node (ref "S11") (pin "3") (pinfunction "VCC_3") (pintype "power_in"))
    )
    (net (code "14") (name "/B12") (class "Default")
      (node (ref "S12") (pin "1") (pinfunction "OUT_1") (pintype "output"))
    )
    (net (code "15") (name "/B13") (class "Default")
      (node (ref "S13") (pin "3") (pinfunction "VCC_3") (pintype "power_in"))
    )
    (net (code "16") (name "/B14") (class "Default")
      (node (ref "S14") (pin "1") (pinfunction "OUT_1") (pintype "output"))
    )
    (net (code "17") (name "/B15") (class "Default")
      (node (ref "S15") (pin "3") (pinfunction "VCC_3") (pintype "power_in"))
    )
    (net (code "18") (name "/B16") (class "Default")
      (node (ref "S16") (pin "1") (pinfunction "OUT_1") (pintype "output"))
    )
    (net (code "19") (name "/B17") (class "Default")
      (node (ref "S17") (pin "3") (pinfunction "VCC_3") (pintype "power_in"))
    )
    (net (code "20") (name "/B18") (class "Default")
      (node (ref "S18") (pin "1") (pinfunction "OUT_1") (pintype "output"))
    )
    (net (code "21") (name "/B19") (class "Default")
      (node (ref "S19") (pin "3") (pinfunction "VCC_3") (pintype "power_in"))
    )
    (net (code "22") (name "/B20") (class "Default")
      (node (ref "S20") (pin "1") (pinfunction "OUT_1") (pintype "output"))
    )
    (net (code "23") (name "/M1_INA") (class "Default")
      (node (ref "M1+") (pin "A") (pinfunction "A_A") (pintype "passive"))
      (node (ref "R5") (pin "1") (pinfunction "1_1") (pintype "passive"))
    )
    (net (code "24") (name "/M1_INB") (class "Default")
      (node (ref "M1-") (pin "A") (pinfunction "A_A") (pintype "passive"))
      (node (ref "R6") (pin "1") (pinfunction "1_1") (pintype "passive"))
    )
    (net (code "25") (name "/M1_OUTA") (class "Default")
      (node (ref "DRV1") (pin "15") (pinfunction "OUT_A_2_15") (pintype "bidirectional"))
      (node (ref "DRV1") (pin "2") (pinfunction "OUT_A_1_2") (pintype "bidirectional"))
    )
    (net (code "26") (name "/M1_OUTB") (class "Default")
      (node (ref "DRV1") (pin "10") (pinfunction "OUT_B_2_10") (pintype "bidirectional"))
      (node (ref "DRV1") (pin "7") (pinfunction "OUT_B_1_7") (pintype "bidirectional"))
    )
    (net (code "27") (name "/M1_PWM") (class "Default")
      (node (ref "R8") (pin "2") (pinfunction "2_2") (pintype "passive"))
    )
    (net (code "28") (name "/M2_INA") (class "Default")
      (node (ref "M2+") (pin "A") (pinfunction "A_A") (pintype "passive"))
      (node (ref "R13") (pin "1") (pinfunction "1_1") (pintype "passive"))
    )
    (net (code "29") (name "/M2_INB") (class "Default")
      (node (ref "M2-") (pin "A") (pinfunction "A_A") (pintype "passive"))
      (node (ref "R14") (pin "1") (pinfunction "1_1") (pintype "passive"))
    )
    (net (code "30") (name "/M2_OUTA") (class "Default")
      (node (ref "DRV2") (pin "15") (pinfunction "OUT_A_2_15") (pintype "bidirectional"))
      (node (ref "DRV2") (pin "2") (pinfunction "OUT_A_1_2") (pintype "bidirectional"))
      (node (ref "M2") (pin "2") (pinfunction "2_2") (pintype "bidirectional"))
    )
    (net (code "31") (name "/M2_OUTB") (class "Default")
      (node (ref "DRV2") (pin "10") (pinfunction "OUT_B_2_10") (pintype "bidirectional"))
      (node (ref "DRV2") (pin "7") (pinfunction "OUT_B_1_7") (pintype "bidirectional"))
      (node (ref "M1") (pin "1") (pinfunction "1_1") (pintype "bidirectional"))
      (node (ref "M2") (pin "1") (pinfunction "1_1") (pintype "bidirectional"))
    )
    (net (code "32") (name "/M2_PWM") (class "Default")
      (node (ref "R16") (pin "2") (pinfunction "2_2") (pintype "passive"))
    )
    (net (code "33") (name "/M3_INA") (class "Default")
      (node (ref "M3+") (pin "A") (pinfunction "A_A") (pintype "passive"))
      (node (ref "R9") (pin "1") (pinfunction "1_1") (pintype "passive"))
    )
    (net (code "34") (name "/M3_INB") (class "Default")
      (node (ref "M3-") (pin "A") (pinfunction "A_A") (pintype "passive"))
      (node (ref "R10") (pin "1") (pinfunction "1_1") (pintype "passive"))
    )
    (net (code "35") (name "/M3_OUTA") (class "Default")
      (node (ref "DRV3") (pin "15") (pinfunction "OUT_A_2_15") (pintype "bidirectional"))
      (node (ref "DRV3") (pin "2") (pinfunction "OUT_A_1_2") (pintype "bidirectional"))
      (node (ref "M1") (pin "2") (pinfunction "2_2") (pintype "bidirectional"))
      (node (ref "M3") (pin "2") (pinfunction "2_2") (pintype "bidirectional"))
    )
    (net (code "36") (name "/M3_OUTB") (class "Default")
      (node (ref "DRV3") (pin "10") (pinfunction "OUT_B_2_10") (pintype "bidirectional"))
      (node (ref "DRV3") (pin "7") (pinfunction "OUT_B_1_7") (pintype "bidirectional"))
      (node (ref "M3") (pin "1") (pinfunction "1_1") (pintype "bidirectional"))
    )
    (net (code "37") (name "/M3_PWM") (class "Default")
      (node (ref "R12") (pin "2") (pinfunction "2_2") (pintype "passive"))
    )
    (net (code "38") (name "/M4_INA") (class "Default")
      (node (ref "M4+") (pin "A") (pinfunction "A_A") (pintype "passive"))
      (node (ref "R17") (pin "1") (pinfunction "1_1") (pintype "passive"))
    )
    (net (code "39") (name "/M4_INB") (class "Default")
      (node (ref "M4-") (pin "A") (pinfunction "A_A") (pintype "passive"))
      (node (ref "R18") (pin "1") (pinfunction "1_1") (pintype "passive"))
    )
    (net (code "40") (name "/M4_OUTA") (class "Default")
      (node (ref "DRV4") (pin "15") (pinfunction "OUT_A_2_15") (pintype "bidirectional"))
      (node (ref "DRV4") (pin "2") (pinfunction "OUT_A_1_2") (pintype "bidirectional"))
      (node (ref "M4") (pin "2") (pinfunction "2_2") (pintype "bidirectional"))
    )
    (net (code "41") (name "/M4_OUTB") (class "Default")
      (node (ref "DRV4") (pin "10") (pinfunction "OUT_B_2_10") (pintype "bidirectional"))
      (node (ref "DRV4") (pin "7") (pinfunction "OUT_B_1_7") (pintype "bidirectional"))
      (node (ref "M4") (pin "1") (pinfunction "1_1") (pintype "bidirectional"))
    )
    (net (code "42") (name "/M4_PWM") (class "Default")
      (node (ref "R20") (pin "2") (pinfunction "2_2") (pintype "passive"))
    )
    (net (code "43") (name "/RXX") (class "Default")
      (node (ref "U$2") (pin "P4") (pinfunction "P4_P4") (pintype "bidirectional"))
    )
    (net (code "44") (name "/SCL") (class "Default")
      (node (ref "R21") (pin "1") (pinfunction "1_1") (pintype "passive"))
      (node (ref "U$3") (pin "SCL") (pinfunction "SCL_SCL") (pintype "bidirectional"))
    )
    (net (code "45") (name "/SDA") (class "Default")
      (node (ref "R22") (pin "1") (pinfunction "1_1") (pintype "passive"))
      (node (ref "U$3") (pin "SDA") (pinfunction "SDA_SDA") (pintype "bidirectional"))
    )
    (net (code "46") (name "/TXX") (class "Default")
      (node (ref "U$2") (pin "P5") (pinfunction "P5_P5") (pintype "bidirectional"))
    )
    (net (code "47") (name "/VBAT") (class "Default")
      (node (ref "BAT_CON") (pin "+") (pinfunction "+_+") (pintype "passive"))
      (node (ref "R_BAT") (pin "1") (pinfunction "1_1") (pintype "passive"))
      (node (ref "SW_ELETT") (pin "1") (pinfunction "O_1") (pintype "passive"))
      (node (ref "SW_MOT") (pin "1") (pinfunction "O_1") (pintype "passive"))
    )
    (net (code "48") (name "GND") (class "Default")
      (node (ref "BAT_CON") (pin "-") (pinfunction "-_-") (pintype "passive"))
      (node (ref "BT_CON") (pin "2") (pinfunction "2_2") (pintype "bidirectional"))
      (node (ref "C10") (pin "2") (pinfunction "2_2") (pintype "passive"))
      (node (ref "C19") (pin "2") (pinfunction "2_2") (pintype "passive"))
      (node (ref "C2") (pin "2") (pinfunction "2_2") (pintype "passive"))
      (node (ref "C20") (pin "2") (pinfunction "2_2") (pintype "passive"))
      (node (ref "C3") (pin "2") (pinfunction "2_2") (pintype "passive"))
      (node (ref "C4") (pin "2") (pinfunction "2_2") (pintype "passive"))
      (node (ref "C5") (pin "2") (pinfunction "2_2") (pintype "passive"))
      (node (ref "C6") (pin "2") (pinfunction "2_2") (pintype "passive"))
      (node (ref "C7") (pin "2") (pinfunction "-_2") (pintype "bidirectional"))
      (node (ref "C8") (pin "2") (pinfunction "2_2") (pintype "passive"))
      (node (ref "CB1") (pin "2") (pinfunction "2_2") (pintype "passive"))
      (node (ref "CB2") (pin "2") (pinfunction "2_2") (pintype "passive"))
      (node (ref "CB3") (pin "2") (pinfunction "2_2") (pintype "passive"))
      (node (ref "CB4") (pin "2") (pinfunction "2_2") (pintype "passive"))
      (node (ref "CB5") (pin "2") (pinfunction "2_2") (pintype "passive"))
      (node (ref "EXTR_PWR") (pin "2") (pinfunction "2_2") (pintype "bidirectional"))
      (node (ref "IC1") (pin "4") (pinfunction "GND_4") (pintype "power_in"))
      (node (ref "IC1") (pin "8") (pinfunction "GND_EP_8") (pintype "power_in"))
      (node (ref "LS_1") (pin "4") (pinfunction "4_4") (pintype "bidirectional"))
      (node (ref "LS_2") (pin "4") (pinfunction "4_4") (pintype "bidirectional"))
      (node (ref "LS_3") (pin "4") (pinfunction "4_4") (pintype "bidirectional"))
      (node (ref "LS_4") (pin "4") (pinfunction "4_4") (pintype "bidirectional"))
      (node (ref "L_BAT") (pin "C") (pinfunction "C_C") (pintype "passive"))
      (node (ref "L_ELETT") (pin "C") (pinfunction "C_C") (pintype "passive"))
      (node (ref "L_MOT") (pin "C") (pinfunction "C_C") (pintype "passive"))
      (node (ref "R11") (pin "2") (pinfunction "2_2") (pintype "passive"))
      (node (ref "R15") (pin "2") (pinfunction "2_2") (pintype "passive"))
      (node (ref "R19") (pin "2") (pinfunction "2_2") (pintype "passive"))
      (node (ref "R2") (pin "1") (pinfunction "1_1") (pintype "passive"))
      (node (ref "R7") (pin "2") (pinfunction "2_2") (pintype "passive"))
      (node (ref "S1") (pin "2") (pinfunction "GND_2") (pintype "power_in"))
      (node (ref "S10") (pin "2") (pinfunction "GND_2") (pintype "power_in"))
      (node (ref "S11") (pin "2") (pinfunction "GND_2") (pintype "power_in"))
      (node (ref "S12") (pin "2") (pinfunction "GND_2") (pintype "power_in"))
      (node (ref "S13") (pin "2") (pinfunction "GND_2") (pintype "power_in"))
      (node (ref "S14") (pin "2") (pinfunction "GND_2") (pintype "power_in"))
      (node (ref "S15") (pin "2") (pinfunction "GND_2") (pintype "power_in"))
      (node (ref "S16") (pin "2") (pinfunction "GND_2") (pintype "power_in"))
      (node (ref "S17") (pin "2") (pinfunction "GND_2") (pintype "power_in"))
      (node (ref "S18") (pin "2") (pinfunction "GND_2") (pintype "power_in"))
      (node (ref "S19") (pin "2") (pinfunction "GND_2") (pintype "power_in"))
      (node (ref "S2") (pin "2") (pinfunction "GND_2") (pintype "power_in"))
      (node (ref "S20") (pin "2") (pinfunction "GND_2") (pintype "power_in"))
      (node (ref "S3") (pin "2") (pinfunction "GND_2") (pintype "power_in"))
      (node (ref "S4") (pin "2") (pinfunction "GND_2") (pintype "power_in"))
      (node (ref "S5") (pin "2") (pinfunction "GND_2") (pintype "power_in"))
      (node (ref "S6") (pin "2") (pinfunction "GND_2") (pintype "power_in"))
      (node (ref "S7") (pin "2") (pinfunction "GND_2") (pintype "power_in"))
      (node (ref "S8") (pin "2") (pinfunction "GND_2") (pintype "power_in"))
      (node (ref "S9") (pin "2") (pinfunction "GND_2") (pintype "power_in"))
      (node (ref "SW_ELETT") (pin "3") (pinfunction "S_3") (pintype "passive"))
      (node (ref "SW_MOT") (pin "3") (pinfunction "S_3") (pintype "passive"))
      (node (ref "U$1") (pin "GND1") (pinfunction "GND1_GND1") (pintype "bidirectional"))
      (node (ref "U$1") (pin "GND2") (pinfunction "GND2_GND2") (pintype "bidirectional"))
      (node (ref "U$1") (pin "GND3") (pinfunction "GND3_GND3") (pintype "bidirectional"))
      (node (ref "U$1") (pin "GND4") (pinfunction "GND4_GND4") (pintype "bidirectional"))
      (node (ref "U$1") (pin "GND5") (pinfunction "GND5_GND5") (pintype "bidirectional"))
      (node (ref "U$1") (pin "GND6") (pinfunction "GND6_GND6") (pintype "bidirectional"))
      (node (ref "U$2") (pin "GND") (pinfunction "GND_GND") (pintype "bidirectional"))
      (node (ref "U$2") (pin "PAD1") (pinfunction "PAD1_PAD1") (pintype "bidirectional"))
      (node (ref "U$2") (pin "PAD2") (pinfunction "PAD2_PAD2") (pintype "bidirectional"))
      (node (ref "U$3") (pin "GND") (pinfunction "GND_GND") (pintype "bidirectional"))
    )
    (net (code "49") (name "Net-(DRV1-IN_A)") (class "Default")
      (node (ref "DRV1") (pin "3") (pinfunction "IN_A_3") (pintype "bidirectional"))
      (node (ref "R5") (pin "2") (pinfunction "2_2") (pintype "passive"))
    )
    (net (code "50") (name "Net-(DRV1-IN_B)") (class "Default")
      (node (ref "DRV1") (pin "6") (pinfunction "IN_B_6") (pintype "bidirectional"))
      (node (ref "R6") (pin "2") (pinfunction "2_2") (pintype "passive"))
    )
    (net (code "51") (name "Net-(DRV1-PWM)") (class "Default")
      (node (ref "DRV1") (pin "11") (pinfunction "PWM_11") (pintype "bidirectional"))
      (node (ref "R8") (pin "1") (pinfunction "1_1") (pintype "passive"))
    )
    (net (code "52") (name "Net-(DRV2-IN_A)") (class "Default")
      (node (ref "DRV2") (pin "3") (pinfunction "IN_A_3") (pintype "bidirectional"))
      (node (ref "R13") (pin "2") (pinfunction "2_2") (pintype "passive"))
    )
    (net (code "53") (name "Net-(DRV2-IN_B)") (class "Default")
      (node (ref "DRV2") (pin "6") (pinfunction "IN_B_6") (pintype "bidirectional"))
      (node (ref "R14") (pin "2") (pinfunction "2_2") (pintype "passive"))
    )
    (net (code "54") (name "Net-(DRV2-PWM)") (class "Default")
      (node (ref "DRV2") (pin "11") (pinfunction "PWM_11") (pintype "bidirectional"))
      (node (ref "R16") (pin "1") (pinfunction "1_1") (pintype "passive"))
    )
    (net (code "55") (name "Net-(DRV3-IN_A)") (class "Default")
      (node (ref "DRV3") (pin "3") (pinfunction "IN_A_3") (pintype "bidirectional"))
      (node (ref "R9") (pin "2") (pinfunction "2_2") (pintype "passive"))
    )
    (net (code "56") (name "Net-(DRV3-IN_B)") (class "Default")
      (node (ref "DRV3") (pin "6") (pinfunction "IN_B_6") (pintype "bidirectional"))
      (node (ref "R10") (pin "2") (pinfunction "2_2") (pintype "passive"))
    )
    (net (code "57") (name "Net-(DRV3-PWM)") (class "Default")
      (node (ref "DRV3") (pin "11") (pinfunction "PWM_11") (pintype "bidirectional"))
      (node (ref "R12") (pin "1") (pinfunction "1_1") (pintype "passive"))
    )
    (net (code "58") (name "Net-(DRV4-IN_A)") (class "Default")
      (node (ref "DRV4") (pin "3") (pinfunction "IN_A_3") (pintype "bidirectional"))
      (node (ref "R17") (pin "2") (pinfunction "2_2") (pintype "passive"))
    )
    (net (code "59") (name "Net-(DRV4-IN_B)") (class "Default")
      (node (ref "DRV4") (pin "6") (pinfunction "IN_B_6") (pintype "bidirectional"))
      (node (ref "R18") (pin "2") (pinfunction "2_2") (pintype "passive"))
    )
    (net (code "60") (name "Net-(DRV4-PWM)") (class "Default")
      (node (ref "DRV4") (pin "11") (pinfunction "PWM_11") (pintype "bidirectional"))
      (node (ref "R20") (pin "1") (pinfunction "1_1") (pintype "passive"))
    )
    (net (code "61") (name "Net-(IC1-FB)") (class "Default")
      (node (ref "C9") (pin "1") (pinfunction "1_1") (pintype "passive"))
      (node (ref "IC1") (pin "6") (pinfunction "FB_6") (pintype "bidirectional"))
      (node (ref "R2") (pin "2") (pinfunction "2_2") (pintype "passive"))
      (node (ref "R3") (pin "2") (pinfunction "2_2") (pintype "passive"))
    )
    (net (code "62") (name "Net-(IC1-RON)") (class "Default")
      (node (ref "IC1") (pin "2") (pinfunction "RON_2") (pintype "bidirectional"))
      (node (ref "R1") (pin "2") (pinfunction "2_2") (pintype "passive"))
    )
    (net (code "63") (name "Net-(IC1-SS)") (class "Default")
      (node (ref "C4") (pin "1") (pinfunction "1_1") (pintype "passive"))
      (node (ref "IC1") (pin "5") (pinfunction "SS_5") (pintype "bidirectional"))
    )
    (net (code "64") (name "Net-(IC1-VOUT)") (class "Default")
      (node (ref "IC1") (pin "7") (pinfunction "VOUT_7") (pintype "output"))
      (node (ref "R_ELETT") (pin "2") (pinfunction "2_2") (pintype "passive"))
    )
    (net (code "65") (name "Net-(L_BAT-PadA)") (class "Default")
      (node (ref "L_BAT") (pin "A") (pinfunction "A_A") (pintype "passive"))
      (node (ref "R_BAT") (pin "2") (pinfunction "2_2") (pintype "passive"))
    )
    (net (code "66") (name "Net-(L_ELETT-PadA)") (class "Default")
      (node (ref "L_ELETT") (pin "A") (pinfunction "A_A") (pintype "passive"))
      (node (ref "R_ELETT") (pin "1") (pinfunction "1_1") (pintype "passive"))
    )
    (net (code "67") (name "Net-(L_MOT-PadA)") (class "Default")
      (node (ref "L_MOT") (pin "A") (pinfunction "A_A") (pintype "passive"))
      (node (ref "R_MOT") (pin "1") (pinfunction "1_1") (pintype "passive"))
    )
    (net (code "68") (name "Net-(M1+-PadC)") (class "Default")
      (node (ref "M1+") (pin "C") (pinfunction "C_C") (pintype "passive"))
      (node (ref "M1-") (pin "C") (pinfunction "C_C") (pintype "passive"))
      (node (ref "R7") (pin "1") (pinfunction "1_1") (pintype "passive"))
    )
    (net (code "69") (name "Net-(M2+-PadC)") (class "Default")
      (node (ref "M2+") (pin "C") (pinfunction "C_C") (pintype "passive"))
      (node (ref "M2-") (pin "C") (pinfunction "C_C") (pintype "passive"))
      (node (ref "R15") (pin "1") (pinfunction "1_1") (pintype "passive"))
    )
    (net (code "70") (name "Net-(M3+-PadC)") (class "Default")
      (node (ref "M3+") (pin "C") (pinfunction "C_C") (pintype "passive"))
      (node (ref "M3-") (pin "C") (pinfunction "C_C") (pintype "passive"))
      (node (ref "R11") (pin "1") (pinfunction "1_1") (pintype "passive"))
    )
    (net (code "71") (name "Net-(M4+-PadC)") (class "Default")
      (node (ref "M4+") (pin "C") (pinfunction "C_C") (pintype "passive"))
      (node (ref "M4-") (pin "C") (pinfunction "C_C") (pintype "passive"))
      (node (ref "R19") (pin "1") (pinfunction "1_1") (pintype "passive"))
    )
    (net (code "72") (name "Net-(S1-OUT)") (class "Default")
      (node (ref "CB1") (pin "1") (pinfunction "1_1") (pintype "passive"))
      (node (ref "RB1") (pin "2") (pinfunction "2_2") (pintype "passive"))
      (node (ref "S1") (pin "1") (pinfunction "OUT_1") (pintype "output"))
      (node (ref "S2") (pin "3") (pinfunction "VCC_3") (pintype "power_in"))
      (node (ref "S3") (pin "1") (pinfunction "OUT_1") (pintype "output"))
      (node (ref "S4") (pin "3") (pinfunction "VCC_3") (pintype "power_in"))
    )
    (net (code "73") (name "Net-(S5-OUT)") (class "Default")
      (node (ref "CB2") (pin "1") (pinfunction "1_1") (pintype "passive"))
      (node (ref "RB2") (pin "2") (pinfunction "2_2") (pintype "passive"))
      (node (ref "S5") (pin "1") (pinfunction "OUT_1") (pintype "output"))
      (node (ref "S6") (pin "3") (pinfunction "VCC_3") (pintype "power_in"))
      (node (ref "S7") (pin "1") (pinfunction "OUT_1") (pintype "output"))
      (node (ref "S8") (pin "3") (pinfunction "VCC_3") (pintype "power_in"))
    )
    (net (code "74") (name "Net-(S10-VCC)") (class "Default")
      (node (ref "CB3") (pin "1") (pinfunction "1_1") (pintype "passive"))
      (node (ref "RB3") (pin "2") (pinfunction "2_2") (pintype "passive"))
      (node (ref "S10") (pin "3") (pinfunction "VCC_3") (pintype "power_in"))
      (node (ref "S11") (pin "1") (pinfunction "OUT_1") (pintype "output"))
      (node (ref "S12") (pin "3") (pinfunction "VCC_3") (pintype "power_in"))
      (node (ref "S9") (pin "1") (pinfunction "OUT_1") (pintype "output"))
    )
    (net (code "75") (name "Net-(S13-OUT)") (class "Default")
      (node (ref "CB4") (pin "1") (pinfunction "1_1") (pintype "passive"))
      (node (ref "RB4") (pin "2") (pinfunction "2_2") (pintype "passive"))
      (node (ref "S13") (pin "1") (pinfunction "OUT_1") (pintype "output"))
      (node (ref "S14") (pin "3") (pinfunction "VCC_3") (pintype "power_in"))
      (node (ref "S15") (pin "1") (pinfunction "OUT_1") (pintype "output"))
      (node (ref "S16") (pin "3") (pinfunction "VCC_3") (pintype "power_in"))
    )
    (net (code "76") (name "Net-(S17-OUT)") (class "Default")
      (node (ref "CB5") (pin "1") (pinfunction "1_1") (pintype "passive"))
      (node (ref "RB5") (pin "2") (pinfunction "2_2") (pintype "passive"))
      (node (ref "S17") (pin "1") (pinfunction "OUT_1") (pintype "output"))
      (node (ref "S18") (pin "3") (pinfunction "VCC_3") (pintype "power_in"))
      (node (ref "S19") (pin "1") (pinfunction "OUT_1") (pintype "output"))
      (node (ref "S20") (pin "3") (pinfunction "VCC_3") (pintype "power_in"))
    )
    (net (code "77") (name "V-") (class "Default")
      (node (ref "C1") (pin "2") (pinfunction "-_2") (pintype "bidirectional"))
      (node (ref "C11") (pin "-") (pinfunction "-_-") (pintype "passive"))
      (node (ref "C12") (pin "2") (pinfunction "2_2") (pintype "passive"))
      (node (ref "C13") (pin "-") (pinfunction "-_-") (pintype "passive"))
      (node (ref "C14") (pin "2") (pinfunction "2_2") (pintype "passive"))
      (node (ref "C15") (pin "-") (pinfunction "-_-") (pintype "passive"))
      (node (ref "C16") (pin "2") (pinfunction "2_2") (pintype "passive"))
      (node (ref "C17") (pin "-") (pinfunction "-_-") (pintype "passive"))
      (node (ref "C18") (pin "2") (pinfunction "2_2") (pintype "passive"))
      (node (ref "DRV1") (pin "1") (pinfunction "GND_A_1_1") (pintype "bidirectional"))
      (node (ref "DRV1") (pin "16") (pinfunction "GND_A_2_16") (pintype "bidirectional"))
      (node (ref "DRV1") (pin "8") (pinfunction "GND_B_1_8") (pintype "bidirectional"))
      (node (ref "DRV1") (pin "9") (pinfunction "GND_B_2_9") (pintype "bidirectional"))
      (node (ref "DRV2") (pin "1") (pinfunction "GND_A_1_1") (pintype "bidirectional"))
      (node (ref "DRV2") (pin "16") (pinfunction "GND_A_2_16") (pintype "bidirectional"))
      (node (ref "DRV2") (pin "8") (pinfunction "GND_B_1_8") (pintype "bidirectional"))
      (node (ref "DRV2") (pin "9") (pinfunction "GND_B_2_9") (pintype "bidirectional"))
      (node (ref "DRV3") (pin "1") (pinfunction "GND_A_1_1") (pintype "bidirectional"))
      (node (ref "DRV3") (pin "16") (pinfunction "GND_A_2_16") (pintype "bidirectional"))
      (node (ref "DRV3") (pin "8") (pinfunction "GND_B_1_8") (pintype "bidirectional"))
      (node (ref "DRV3") (pin "9") (pinfunction "GND_B_2_9") (pintype "bidirectional"))
      (node (ref "DRV4") (pin "1") (pinfunction "GND_A_1_1") (pintype "bidirectional"))
      (node (ref "DRV4") (pin "16") (pinfunction "GND_A_2_16") (pintype "bidirectional"))
      (node (ref "DRV4") (pin "8") (pinfunction "GND_B_1_8") (pintype "bidirectional"))
      (node (ref "DRV4") (pin "9") (pinfunction "GND_B_2_9") (pintype "bidirectional"))
    )
    (net (code "78") (name "VMOT") (class "Default")
      (node (ref "C1") (pin "1") (pinfunction "+_1") (pintype "bidirectional"))
      (node (ref "R_MOT") (pin "2") (pinfunction "2_2") (pintype "passive"))
      (node (ref "SW_MOT") (pin "2") (pinfunction "P_2") (pintype "passive"))
    )
    (net (code "79") (name "unconnected-(BT_CON-Pad3)") (class "Default")
      (node (ref "BT_CON") (pin "3") (pinfunction "3_3") (pintype "bidirectional"))
    )
    (net (code "80") (name "unconnected-(BT_CON-Pad4)") (class "Default")
      (node (ref "BT_CON") (pin "4") (pinfunction "4_4") (pintype "bidirectional"))
    )
    (net (code "81") (name "unconnected-(DRV1-CS-Pad13)") (class "Default")
      (node (ref "DRV1") (pin "13") (pinfunction "CS_13") (pintype "bidirectional"))
    )
    (net (code "82") (name "unconnected-(DRV1-SEL_0-Pad14)") (class "Default")
      (node (ref "DRV1") (pin "14") (pinfunction "SEL_0_14") (pintype "bidirectional"))
    )
    (net (code "83") (name "unconnected-(DRV2-CS-Pad13)") (class "Default")
      (node (ref "DRV2") (pin "13") (pinfunction "CS_13") (pintype "bidirectional"))
    )
    (net (code "84") (name "unconnected-(DRV2-SEL_0-Pad14)") (class "Default")
      (node (ref "DRV2") (pin "14") (pinfunction "SEL_0_14") (pintype "bidirectional"))
    )
    (net (code "85") (name "unconnected-(DRV3-CS-Pad13)") (class "Default")
      (node (ref "DRV3") (pin "13") (pinfunction "CS_13") (pintype "bidirectional"))
    )
    (net (code "86") (name "unconnected-(DRV3-SEL_0-Pad14)") (class "Default")
      (node (ref "DRV3") (pin "14") (pinfunction "SEL_0_14") (pintype "bidirectional"))
    )
    (net (code "87") (name "unconnected-(DRV4-CS-Pad13)") (class "Default")
      (node (ref "DRV4") (pin "13") (pinfunction "CS_13") (pintype "bidirectional"))
    )
    (net (code "88") (name "unconnected-(DRV4-SEL_0-Pad14)") (class "Default")
      (node (ref "DRV4") (pin "14") (pinfunction "SEL_0_14") (pintype "bidirectional"))
    )
    (net (code "89") (name "unconnected-(IC1-EN-Pad3)") (class "Default")
      (node (ref "IC1") (pin "3") (pinfunction "EN_3") (pintype "bidirectional"))
    )
    (net (code "90") (name "unconnected-(LS_1-Pad2)") (class "Default")
      (node (ref "LS_1") (pin "2") (pinfunction "2_2") (pintype "bidirectional"))
    )
    (net (code "91") (name "unconnected-(LS_1-Pad3)") (class "Default")
      (node (ref "LS_1") (pin "3") (pinfunction "3_3") (pintype "bidirectional"))
    )
    (net (code "92") (name "unconnected-(LS_2-Pad2)") (class "Default")
      (node (ref "LS_2") (pin "2") (pinfunction "2_2") (pintype "bidirectional"))
    )
    (net (code "93") (name "unconnected-(LS_2-Pad3)") (class "Default")
      (node (ref "LS_2") (pin "3") (pinfunction "3_3") (pintype "bidirectional"))
    )
    (net (code "94") (name "unconnected-(LS_3-Pad2)") (class "Default")
      (node (ref "LS_3") (pin "2") (pinfunction "2_2") (pintype "bidirectional"))
    )
    (net (code "95") (name "unconnected-(LS_3-Pad3)") (class "Default")
      (node (ref "LS_3") (pin "3") (pinfunction "3_3") (pintype "bidirectional"))
    )
    (net (code "96") (name "unconnected-(LS_4-Pad2)") (class "Default")
      (node (ref "LS_4") (pin "2") (pinfunction "2_2") (pintype "bidirectional"))
    )
    (net (code "97") (name "unconnected-(LS_4-Pad3)") (class "Default")
      (node (ref "LS_4") (pin "3") (pinfunction "3_3") (pintype "bidirectional"))
    )
    (net (code "98") (name "unconnected-(SV1-Pad1)") (class "Default")
      (node (ref "SV1") (pin "1") (pinfunction "1_1") (pintype "passive"))
    )
    (net (code "99") (name "unconnected-(SV1-Pad2)") (class "Default")
      (node (ref "SV1") (pin "2") (pinfunction "2_2") (pintype "passive"))
    )
    (net (code "100") (name "unconnected-(SV1-Pad3)") (class "Default")
      (node (ref "SV1") (pin "3") (pinfunction "3_3") (pintype "passive"))
    )
    (net (code "101") (name "unconnected-(SV1-Pad4)") (class "Default")
      (node (ref "SV1") (pin "4") (pinfunction "4_4") (pintype "passive"))
    )
    (net (code "102") (name "unconnected-(SV1-Pad5)") (class "Default")
      (node (ref "SV1") (pin "5") (pinfunction "5_5") (pintype "passive"))
    )
    (net (code "103") (name "unconnected-(SV1-Pad6)") (class "Default")
      (node (ref "SV1") (pin "6") (pinfunction "6_6") (pintype "passive"))
    )
    (net (code "104") (name "unconnected-(SV1-Pad7)") (class "Default")
      (node (ref "SV1") (pin "7") (pinfunction "7_7") (pintype "passive"))
    )
    (net (code "105") (name "unconnected-(SV1-Pad8)") (class "Default")
      (node (ref "SV1") (pin "8") (pinfunction "8_8") (pintype "passive"))
    )
    (net (code "106") (name "unconnected-(SV1-Pad9)") (class "Default")
      (node (ref "SV1") (pin "9") (pinfunction "9_9") (pintype "passive"))
    )
    (net (code "107") (name "unconnected-(SV1-Pad10)") (class "Default")
      (node (ref "SV1") (pin "10") (pinfunction "10_10") (pintype "passive"))
    )
    (net (code "108") (name "unconnected-(SV1-Pad11)") (class "Default")
      (node (ref "SV1") (pin "11") (pinfunction "11_11") (pintype "passive"))
    )
    (net (code "109") (name "unconnected-(SV1-Pad12)") (class "Default")
      (node (ref "SV1") (pin "12") (pinfunction "12_12") (pintype "passive"))
    )
    (net (code "110") (name "unconnected-(SV2-Pad1)") (class "Default")
      (node (ref "SV2") (pin "1") (pinfunction "1_1") (pintype "passive"))
    )
    (net (code "111") (name "unconnected-(SV2-Pad2)") (class "Default")
      (node (ref "SV2") (pin "2") (pinfunction "2_2") (pintype "passive"))
    )
    (net (code "112") (name "unconnected-(SV2-Pad5)") (class "Default")
      (node (ref "SV2") (pin "5") (pinfunction "5_5") (pintype "passive"))
    )
    (net (code "113") (name "unconnected-(SV2-Pad6)") (class "Default")
      (node (ref "SV2") (pin "6") (pinfunction "6_6") (pintype "passive"))
    )
    (net (code "114") (name "unconnected-(SV2-Pad7)") (class "Default")
      (node (ref "SV2") (pin "7") (pinfunction "7_7") (pintype "passive"))
    )
    (net (code "115") (name "unconnected-(SV2-Pad8)") (class "Default")
      (node (ref "SV2") (pin "8") (pinfunction "8_8") (pintype "passive"))
    )
    (net (code "116") (name "unconnected-(SV2-Pad9)") (class "Default")
      (node (ref "SV2") (pin "9") (pinfunction "9_9") (pintype "passive"))
    )
    (net (code "117") (name "unconnected-(SV2-Pad10)") (class "Default")
      (node (ref "SV2") (pin "10") (pinfunction "10_10") (pintype "passive"))
    )
    (net (code "118") (name "unconnected-(SV2-Pad11)") (class "Default")
      (node (ref "SV2") (pin "11") (pinfunction "11_11") (pintype "passive"))
    )
    (net (code "119") (name "unconnected-(SV2-Pad12)") (class "Default")
      (node (ref "SV2") (pin "12") (pinfunction "12_12") (pintype "passive"))
    )
    (net (code "120") (name "unconnected-(SV3-Pad1)") (class "Default")
      (node (ref "SV3") (pin "1") (pinfunction "1_1") (pintype "passive"))
    )
    (net (code "121") (name "unconnected-(SV3-Pad2)") (class "Default")
      (node (ref "SV3") (pin "2") (pinfunction "2_2") (pintype "passive"))
    )
    (net (code "122") (name "unconnected-(SV3-Pad3)") (class "Default")
      (node (ref "SV3") (pin "3") (pinfunction "3_3") (pintype "passive"))
    )
    (net (code "123") (name "unconnected-(SV3-Pad4)") (class "Default")
      (node (ref "SV3") (pin "4") (pinfunction "4_4") (pintype "passive"))
    )
    (net (code "124") (name "unconnected-(SV3-Pad5)") (class "Default")
      (node (ref "SV3") (pin "5") (pinfunction "5_5") (pintype "passive"))
    )
    (net (code "125") (name "unconnected-(SV3-Pad6)") (class "Default")
      (node (ref "SV3") (pin "6") (pinfunction "6_6") (pintype "passive"))
    )
    (net (code "126") (name "unconnected-(SV3-Pad7)") (class "Default")
      (node (ref "SV3") (pin "7") (pinfunction "7_7") (pintype "passive"))
    )
    (net (code "127") (name "unconnected-(SV3-Pad8)") (class "Default")
      (node (ref "SV3") (pin "8") (pinfunction "8_8") (pintype "passive"))
    )
    (net (code "128") (name "unconnected-(SV3-Pad9)") (class "Default")
      (node (ref "SV3") (pin "9") (pinfunction "9_9") (pintype "passive"))
    )
    (net (code "129") (name "unconnected-(SV3-Pad10)") (class "Default")
      (node (ref "SV3") (pin "10") (pinfunction "10_10") (pintype "passive"))
    )
    (net (code "130") (name "unconnected-(SV3-Pad11)") (class "Default")
      (node (ref "SV3") (pin "11") (pinfunction "11_11") (pintype "passive"))
    )
    (net (code "131") (name "unconnected-(SV3-Pad12)") (class "Default")
      (node (ref "SV3") (pin "12") (pinfunction "12_12") (pintype "passive"))
    )
    (net (code "132") (name "unconnected-(SV4-Pad1)") (class "Default")
      (node (ref "SV4") (pin "1") (pinfunction "1_1") (pintype "passive"))
    )
    (net (code "133") (name "unconnected-(SV4-Pad2)") (class "Default")
      (node (ref "SV4") (pin "2") (pinfunction "2_2") (pintype "passive"))
    )
    (net (code "134") (name "unconnected-(SV4-Pad3)") (class "Default")
      (node (ref "SV4") (pin "3") (pinfunction "3_3") (pintype "passive"))
    )
    (net (code "135") (name "unconnected-(SV4-Pad4)") (class "Default")
      (node (ref "SV4") (pin "4") (pinfunction "4_4") (pintype "passive"))
    )
    (net (code "136") (name "unconnected-(SV4-Pad5)") (class "Default")
      (node (ref "SV4") (pin "5") (pinfunction "5_5") (pintype "passive"))
    )
    (net (code "137") (name "unconnected-(SV4-Pad6)") (class "Default")
      (node (ref "SV4") (pin "6") (pinfunction "6_6") (pintype "passive"))
    )
    (net (code "138") (name "unconnected-(SV4-Pad7)") (class "Default")
      (node (ref "SV4") (pin "7") (pinfunction "7_7") (pintype "passive"))
    )
    (net (code "139") (name "unconnected-(SV4-Pad8)") (class "Default")
      (node (ref "SV4") (pin "8") (pinfunction "8_8") (pintype "passive"))
    )
    (net (code "140") (name "unconnected-(SV4-Pad9)") (class "Default")
      (node (ref "SV4") (pin "9") (pinfunction "9_9") (pintype "passive"))
    )
    (net (code "141") (name "unconnected-(SV4-Pad10)") (class "Default")
      (node (ref "SV4") (pin "10") (pinfunction "10_10") (pintype "passive"))
    )
    (net (code "142") (name "unconnected-(SV4-Pad11)") (class "Default")
      (node (ref "SV4") (pin "11") (pinfunction "11_11") (pintype "passive"))
    )
    (net (code "143") (name "unconnected-(SV4-Pad12)") (class "Default")
      (node (ref "SV4") (pin "12") (pinfunction "12_12") (pintype "passive"))
    )
    (net (code "144") (name "unconnected-(SV5-Pad1)") (class "Default")
      (node (ref "SV5") (pin "1") (pinfunction "1_1") (pintype "passive"))
    )
    (net (code "145") (name "unconnected-(SV5-Pad2)") (class "Default")
      (node (ref "SV5") (pin "2") (pinfunction "2_2") (pintype "passive"))
    )
    (net (code "146") (name "unconnected-(SV5-Pad3)") (class "Default")
      (node (ref "SV5") (pin "3") (pinfunction "3_3") (pintype "passive"))
    )
    (net (code "147") (name "unconnected-(SV5-Pad4)") (class "Default")
      (node (ref "SV5") (pin "4") (pinfunction "4_4") (pintype "passive"))
    )
    (net (code "148") (name "unconnected-(SV5-Pad5)") (class "Default")
      (node (ref "SV5") (pin "5") (pinfunction "5_5") (pintype "passive"))
    )
    (net (code "149") (name "unconnected-(SV5-Pad6)") (class "Default")
      (node (ref "SV5") (pin "6") (pinfunction "6_6") (pintype "passive"))
    )
    (net (code "150") (name "unconnected-(SV5-Pad7)") (class "Default")
      (node (ref "SV5") (pin "7") (pinfunction "7_7") (pintype "passive"))
    )
    (net (code "151") (name "unconnected-(SV5-Pad8)") (class "Default")
      (node (ref "SV5") (pin "8") (pinfunction "8_8") (pintype "passive"))
    )
    (net (code "152") (name "unconnected-(SV5-Pad9)") (class "Default")
      (node (ref "SV5") (pin "9") (pinfunction "9_9") (pintype "passive"))
    )
    (net (code "153") (name "unconnected-(SV5-Pad10)") (class "Default")
      (node (ref "SV5") (pin "10") (pinfunction "10_10") (pintype "passive"))
    )
    (net (code "154") (name "unconnected-(SV5-Pad11)") (class "Default")
      (node (ref "SV5") (pin "11") (pinfunction "11_11") (pintype "passive"))
    )
    (net (code "155") (name "unconnected-(SV5-Pad12)") (class "Default")
      (node (ref "SV5") (pin "12") (pinfunction "12_12") (pintype "passive"))
    )
    (net (code "156") (name "unconnected-(SV6-Pad1)") (class "Default")
      (node (ref "SV6") (pin "1") (pinfunction "1_1") (pintype "passive"))
    )
    (net (code "157") (name "unconnected-(SV6-Pad2)") (class "Default")
      (node (ref "SV6") (pin "2") (pinfunction "2_2") (pintype "passive"))
    )
    (net (code "158") (name "unconnected-(SV6-Pad3)") (class "Default")
      (node (ref "SV6") (pin "3") (pinfunction "3_3") (pintype "passive"))
    )
    (net (code "159") (name "unconnected-(SV6-Pad4)") (class "Default")
      (node (ref "SV6") (pin "4") (pinfunction "4_4") (pintype "passive"))
    )
    (net (code "160") (name "unconnected-(SV6-Pad5)") (class "Default")
      (node (ref "SV6") (pin "5") (pinfunction "5_5") (pintype "passive"))
    )
    (net (code "161") (name "unconnected-(SV6-Pad6)") (class "Default")
      (node (ref "SV6") (pin "6") (pinfunction "6_6") (pintype "passive"))
    )
    (net (code "162") (name "unconnected-(SV6-Pad7)") (class "Default")
      (node (ref "SV6") (pin "7") (pinfunction "7_7") (pintype "passive"))
    )
    (net (code "163") (name "unconnected-(SV6-Pad10)") (class "Default")
      (node (ref "SV6") (pin "10") (pinfunction "10_10") (pintype "passive"))
    )
    (net (code "164") (name "unconnected-(SV6-Pad11)") (class "Default")
      (node (ref "SV6") (pin "11") (pinfunction "11_11") (pintype "passive"))
    )
    (net (code "165") (name "unconnected-(SV6-Pad12)") (class "Default")
      (node (ref "SV6") (pin "12") (pinfunction "12_12") (pintype "passive"))
    )
    (net (code "166") (name "unconnected-(SV6-Pad13)") (class "Default")
      (node (ref "SV6") (pin "13") (pinfunction "13_13") (pintype "passive"))
    )
    (net (code "167") (name "unconnected-(SV6-Pad14)") (class "Default")
      (node (ref "SV6") (pin "14") (pinfunction "14_14") (pintype "passive"))
    )
    (net (code "168") (name "unconnected-(SV7-Pad1)") (class "Default")
      (node (ref "SV7") (pin "1") (pinfunction "1_1") (pintype "passive"))
    )
    (net (code "169") (name "unconnected-(SV7-Pad2)") (class "Default")
      (node (ref "SV7") (pin "2") (pinfunction "2_2") (pintype "passive"))
    )
    (net (code "170") (name "unconnected-(SV7-Pad3)") (class "Default")
      (node (ref "SV7") (pin "3") (pinfunction "3_3") (pintype "passive"))
    )
    (net (code "171") (name "unconnected-(SV8-Pad1)") (class "Default")
      (node (ref "SV8") (pin "1") (pinfunction "1_1") (pintype "passive"))
    )
    (net (code "172") (name "unconnected-(SV8-Pad2)") (class "Default")
      (node (ref "SV8") (pin "2") (pinfunction "2_2") (pintype "passive"))
    )
    (net (code "173") (name "unconnected-(SV8-Pad3)") (class "Default")
      (node (ref "SV8") (pin "3") (pinfunction "3_3") (pintype "passive"))
    )
    (net (code "174") (name "unconnected-(SV9-Pad1)") (class "Default")
      (node (ref "SV9") (pin "1") (pinfunction "1_1") (pintype "passive"))
    )
    (net (code "175") (name "unconnected-(SV9-Pad2)") (class "Default")
      (node (ref "SV9") (pin "2") (pinfunction "2_2") (pintype "passive"))
    )
    (net (code "176") (name "unconnected-(SV9-Pad3)") (class "Default")
      (node (ref "SV9") (pin "3") (pinfunction "3_3") (pintype "passive"))
    )
    (net (code "177") (name "unconnected-(SV10-Pad1)") (class "Default")
      (node (ref "SV10") (pin "1") (pinfunction "1_1") (pintype "passive"))
    )
    (net (code "178") (name "unconnected-(SV10-Pad2)") (class "Default")
      (node (ref "SV10") (pin "2") (pinfunction "2_2") (pintype "passive"))
    )
    (net (code "179") (name "unconnected-(SV10-Pad3)") (class "Default")
      (node (ref "SV10") (pin "3") (pinfunction "3_3") (pintype "passive"))
    )
    (net (code "180") (name "unconnected-(SV11-Pad1)") (class "Default")
      (node (ref "SV11") (pin "1") (pinfunction "1_1") (pintype "passive"))
    )
    (net (code "181") (name "unconnected-(SV11-Pad2)") (class "Default")
      (node (ref "SV11") (pin "2") (pinfunction "2_2") (pintype "passive"))
    )
    (net (code "182") (name "unconnected-(SV11-Pad3)") (class "Default")
      (node (ref "SV11") (pin "3") (pinfunction "3_3") (pintype "passive"))
    )
    (net (code "183") (name "unconnected-(SV12-Pad1)") (class "Default")
      (node (ref "SV12") (pin "1") (pinfunction "1_1") (pintype "passive"))
    )
    (net (code "184") (name "unconnected-(SV12-Pad2)") (class "Default")
      (node (ref "SV12") (pin "2") (pinfunction "2_2") (pintype "passive"))
    )
    (net (code "185") (name "unconnected-(SV12-Pad3)") (class "Default")
      (node (ref "SV12") (pin "3") (pinfunction "3_3") (pintype "passive"))
    )
    (net (code "186") (name "unconnected-(SV13-Pad1)") (class "Default")
      (node (ref "SV13") (pin "1") (pinfunction "1_1") (pintype "passive"))
    )
    (net (code "187") (name "unconnected-(SV13-Pad2)") (class "Default")
      (node (ref "SV13") (pin "2") (pinfunction "2_2") (pintype "passive"))
    )
    (net (code "188") (name "unconnected-(SV13-Pad3)") (class "Default")
      (node (ref "SV13") (pin "3") (pinfunction "3_3") (pintype "passive"))
    )
    (net (code "189") (name "unconnected-(SV14-Pad1)") (class "Default")
      (node (ref "SV14") (pin "1") (pinfunction "1_1") (pintype "passive"))
    )
    (net (code "190") (name "unconnected-(SV14-Pad2)") (class "Default")
      (node (ref "SV14") (pin "2") (pinfunction "2_2") (pintype "passive"))
    )
    (net (code "191") (name "unconnected-(SV14-Pad3)") (class "Default")
      (node (ref "SV14") (pin "3") (pinfunction "3_3") (pintype "passive"))
    )
    (net (code "192") (name "unconnected-(SV15-Pad1)") (class "Default")
      (node (ref "SV15") (pin "1") (pinfunction "1_1") (pintype "passive"))
    )
    (net (code "193") (name "unconnected-(SV15-Pad2)") (class "Default")
      (node (ref "SV15") (pin "2") (pinfunction "2_2") (pintype "passive"))
    )
    (net (code "194") (name "unconnected-(SV15-Pad3)") (class "Default")
      (node (ref "SV15") (pin "3") (pinfunction "3_3") (pintype "passive"))
    )
    (net (code "195") (name "unconnected-(SV16-Pad1)") (class "Default")
      (node (ref "SV16") (pin "1") (pinfunction "1_1") (pintype "passive"))
    )
    (net (code "196") (name "unconnected-(SV16-Pad2)") (class "Default")
      (node (ref "SV16") (pin "2") (pinfunction "2_2") (pintype "passive"))
    )
    (net (code "197") (name "unconnected-(SV16-Pad3)") (class "Default")
      (node (ref "SV16") (pin "3") (pinfunction "3_3") (pintype "passive"))
    )
    (net (code "198") (name "unconnected-(SV17-Pad1)") (class "Default")
      (node (ref "SV17") (pin "1") (pinfunction "1_1") (pintype "passive"))
    )
    (net (code "199") (name "unconnected-(SV17-Pad2)") (class "Default")
      (node (ref "SV17") (pin "2") (pinfunction "2_2") (pintype "passive"))
    )
    (net (code "200") (name "unconnected-(SV17-Pad3)") (class "Default")
      (node (ref "SV17") (pin "3") (pinfunction "3_3") (pintype "passive"))
    )
    (net (code "201") (name "unconnected-(SV18-Pad1)") (class "Default")
      (node (ref "SV18") (pin "1") (pinfunction "1_1") (pintype "passive"))
    )
    (net (code "202") (name "unconnected-(SV18-Pad2)") (class "Default")
      (node (ref "SV18") (pin "2") (pinfunction "2_2") (pintype "passive"))
    )
    (net (code "203") (name "unconnected-(SV18-Pad3)") (class "Default")
      (node (ref "SV18") (pin "3") (pinfunction "3_3") (pintype "passive"))
    )
    (net (code "204") (name "unconnected-(SV19-Pad1)") (class "Default")
      (node (ref "SV19") (pin "1") (pinfunction "1_1") (pintype "passive"))
    )
    (net (code "205") (name "unconnected-(SV19-Pad2)") (class "Default")
      (node (ref "SV19") (pin "2") (pinfunction "2_2") (pintype "passive"))
    )
    (net (code "206") (name "unconnected-(SV19-Pad3)") (class "Default")
      (node (ref "SV19") (pin "3") (pinfunction "3_3") (pintype "passive"))
    )
    (net (code "207") (name "unconnected-(SV20-Pad1)") (class "Default")
      (node (ref "SV20") (pin "1") (pinfunction "1_1") (pintype "passive"))
    )
    (net (code "208") (name "unconnected-(SV20-Pad2)") (class "Default")
      (node (ref "SV20") (pin "2") (pinfunction "2_2") (pintype "passive"))
    )
    (net (code "209") (name "unconnected-(SV20-Pad3)") (class "Default")
      (node (ref "SV20") (pin "3") (pinfunction "3_3") (pintype "passive"))
    )
    (net (code "210") (name "unconnected-(SV21-Pad1)") (class "Default")
      (node (ref "SV21") (pin "1") (pinfunction "1_1") (pintype "passive"))
    )
    (net (code "211") (name "unconnected-(SV21-Pad2)") (class "Default")
      (node (ref "SV21") (pin "2") (pinfunction "2_2") (pintype "passive"))
    )
    (net (code "212") (name "unconnected-(SV21-Pad3)") (class "Default")
      (node (ref "SV21") (pin "3") (pinfunction "3_3") (pintype "passive"))
    )
    (net (code "213") (name "unconnected-(SV22-Pad1)") (class "Default")
      (node (ref "SV22") (pin "1") (pinfunction "1_1") (pintype "passive"))
    )
    (net (code "214") (name "unconnected-(SV22-Pad2)") (class "Default")
      (node (ref "SV22") (pin "2") (pinfunction "2_2") (pintype "passive"))
    )
    (net (code "215") (name "unconnected-(SV22-Pad3)") (class "Default")
      (node (ref "SV22") (pin "3") (pinfunction "3_3") (pintype "passive"))
    )
    (net (code "216") (name "unconnected-(SV23-Pad1)") (class "Default")
      (node (ref "SV23") (pin "1") (pinfunction "1_1") (pintype "passive"))
    )
    (net (code "217") (name "unconnected-(SV23-Pad2)") (class "Default")
      (node (ref "SV23") (pin "2") (pinfunction "2_2") (pintype "passive"))
    )
    (net (code "218") (name "unconnected-(SV23-Pad3)") (class "Default")
      (node (ref "SV23") (pin "3") (pinfunction "3_3") (pintype "passive"))
    )
    (net (code "219") (name "unconnected-(SV24-Pad1)") (class "Default")
      (node (ref "SV24") (pin "1") (pinfunction "1_1") (pintype "passive"))
    )
    (net (code "220") (name "unconnected-(SV24-Pad2)") (class "Default")
      (node (ref "SV24") (pin "2") (pinfunction "2_2") (pintype "passive"))
    )
    (net (code "221") (name "unconnected-(SV24-Pad3)") (class "Default")
      (node (ref "SV24") (pin "3") (pinfunction "3_3") (pintype "passive"))
    )
    (net (code "222") (name "unconnected-(SV25-Pad1)") (class "Default")
      (node (ref "SV25") (pin "1") (pinfunction "1_1") (pintype "passive"))
    )
    (net (code "223") (name "unconnected-(SV25-Pad2)") (class "Default")
      (node (ref "SV25") (pin "2") (pinfunction "2_2") (pintype "passive"))
    )
    (net (code "224") (name "unconnected-(SV25-Pad3)") (class "Default")
      (node (ref "SV25") (pin "3") (pinfunction "3_3") (pintype "passive"))
    )
    (net (code "225") (name "unconnected-(SV26-Pad1)") (class "Default")
      (node (ref "SV26") (pin "1") (pinfunction "1_1") (pintype "passive"))
    )
    (net (code "226") (name "unconnected-(SV26-Pad2)") (class "Default")
      (node (ref "SV26") (pin "2") (pinfunction "2_2") (pintype "passive"))
    )
    (net (code "227") (name "unconnected-(SV26-Pad3)") (class "Default")
      (node (ref "SV26") (pin "3") (pinfunction "3_3") (pintype "passive"))
    )
    (net (code "228") (name "unconnected-(U$1-5V-Pad+5V)") (class "Default")
      (node (ref "U$1") (pin "+5V") (pinfunction "5V_+5V") (pintype "bidirectional"))
    )
    (net (code "229") (name "unconnected-(U$1-8-TX2{slash}IN1-Pad8-TX2{slash}IN2)") (class "Default")
      (node (ref "U$1") (pin "8-TX2/IN2") (pinfunction "8-TX2/IN1_8-TX2/IN2") (pintype "bidirectional"))
    )
    (net (code "230") (name "unconnected-(U$1-35{slash}TX8-Pad35-TX8)") (class "Default")
      (node (ref "U$1") (pin "35-TX8") (pinfunction "35/TX8_35-TX8") (pintype "bidirectional"))
    )
    (net (code "231") (name "unconnected-(U$1-Pad0-RX1{slash}CS1{slash}CRX2)") (class "Default")
      (node (ref "U$1") (pin "0-RX1/CS1/CRX2") (pinfunction "0-RX1/CS1/CRX2_0-RX1/CS1/CRX2") (pintype "bidirectional"))
    )
    (net (code "232") (name "unconnected-(U$1-Pad1-TX1{slash}MISO1{slash}CTX2)") (class "Default")
      (node (ref "U$1") (pin "1-TX1/MISO1/CTX2") (pinfunction "1-TX1/MISO1/CTX2_1-TX1/MISO1/CTX2") (pintype "bidirectional"))
    )
    (net (code "233") (name "unconnected-(U$1-Pad2-OUT2)") (class "Default")
      (node (ref "U$1") (pin "2-OUT2") (pinfunction "2-OUT2_2-OUT2") (pintype "bidirectional"))
    )
    (net (code "234") (name "unconnected-(U$1-Pad3-LRCLK2)") (class "Default")
      (node (ref "U$1") (pin "3-LRCLK2") (pinfunction "3-LRCLK2_3-LRCLK2") (pintype "bidirectional"))
    )
    (net (code "235") (name "unconnected-(U$1-Pad3V3-1)") (class "Default")
      (node (ref "U$1") (pin "3V3-1") (pinfunction "3V3-1_3V3-1") (pintype "bidirectional"))
    )
    (net (code "236") (name "unconnected-(U$1-Pad3V3-2)") (class "Default")
      (node (ref "U$1") (pin "3V3-2") (pinfunction "3V3-2_3V3-2") (pintype "bidirectional"))
    )
    (net (code "237") (name "unconnected-(U$1-Pad3V3-3)") (class "Default")
      (node (ref "U$1") (pin "3V3-3") (pinfunction "3V3-3_3V3-3") (pintype "bidirectional"))
    )
    (net (code "238") (name "unconnected-(U$1-Pad4-BCLK2)") (class "Default")
      (node (ref "U$1") (pin "4-BCLK2") (pinfunction "4-BCLK2_4-BCLK2") (pintype "bidirectional"))
    )
    (net (code "239") (name "unconnected-(U$1-Pad5-IN2)") (class "Default")
      (node (ref "U$1") (pin "5-IN2") (pinfunction "5-IN2_5-IN2") (pintype "bidirectional"))
    )
    (net (code "240") (name "unconnected-(U$1-Pad6-OUT1D)") (class "Default")
      (node (ref "U$1") (pin "6-OUT1D") (pinfunction "6-OUT1D_6-OUT1D") (pintype "bidirectional"))
    )
    (net (code "241") (name "unconnected-(U$1-Pad7-RX2{slash}OUT1A)") (class "Default")
      (node (ref "U$1") (pin "7-RX2/OUT1A") (pinfunction "7-RX2/OUT1A_7-RX2/OUT1A") (pintype "bidirectional"))
    )
    (net (code "242") (name "unconnected-(U$1-Pad9-OUT1C)") (class "Default")
      (node (ref "U$1") (pin "9-OUT1C") (pinfunction "9-OUT1C_9-OUT1C") (pintype "bidirectional"))
    )
    (net (code "243") (name "unconnected-(U$1-Pad12-MISO{slash}MQSL)") (class "Default")
      (node (ref "U$1") (pin "12-MISO/MQSL") (pinfunction "12-MISO/MQSL_12-MISO/MQSL") (pintype "bidirectional"))
    )
    (net (code "244") (name "unconnected-(U$1-Pad13-SCK{slash}LED)") (class "Default")
      (node (ref "U$1") (pin "13-SCK/LED") (pinfunction "13-SCK/LED_13-SCK/LED") (pintype "bidirectional"))
    )
    (net (code "245") (name "unconnected-(U$1-Pad14-A0{slash}TX3{slash}SPDIF_OUT)") (class "Default")
      (node (ref "U$1") (pin "14-A0/TX3/SPDIF_OUT") (pinfunction "14-A0/TX3/SPDIF_OUT_14-A0/TX3/SPDIF_OUT") (pintype "bidirectional"))
    )
    (net (code "246") (name "unconnected-(U$1-Pad15-A1{slash}RX3{slash}SPDIF_IN)") (class "Default")
      (node (ref "U$1") (pin "15-A1/RX3/SPDIF_IN") (pinfunction "15-A1/RX3/SPDIF_IN_15-A1/RX3/SPDIF_IN") (pintype "bidirectional"))
    )
    (net (code "247") (name "unconnected-(U$1-Pad16-A2{slash}RX4{slash}SCL1)") (class "Default")
      (node (ref "U$1") (pin "16-A2/RX4/SCL1") (pinfunction "16-A2/RX4/SCL1_16-A2/RX4/SCL1") (pintype "bidirectional"))
    )
    (net (code "248") (name "unconnected-(U$1-Pad17-A3{slash}TX4{slash}SDA1)") (class "Default")
      (node (ref "U$1") (pin "17-A3/TX4/SDA1") (pinfunction "17-A3/TX4/SDA1_17-A3/TX4/SDA1") (pintype "bidirectional"))
    )
    (net (code "249") (name "unconnected-(U$1-Pad18-A4{slash}SDA0)") (class "Default")
      (node (ref "U$1") (pin "18-A4/SDA0") (pinfunction "18-A4/SDA0_18-A4/SDA0") (pintype "bidirectional"))
    )
    (net (code "250") (name "unconnected-(U$1-Pad19-A5{slash}SCL0)") (class "Default")
      (node (ref "U$1") (pin "19-A5/SCL0") (pinfunction "19-A5/SCL0_19-A5/SCL0") (pintype "bidirectional"))
    )
    (net (code "251") (name "unconnected-(U$1-Pad20-A6{slash}TX5{slash}LRCLK1)") (class "Default")
      (node (ref "U$1") (pin "20-A6/TX5/LRCLK1") (pinfunction "20-A6/TX5/LRCLK1_20-A6/TX5/LRCLK1") (pintype "bidirectional"))
    )
    (net (code "252") (name "unconnected-(U$1-Pad21-A7{slash}RX5{slash}BCLK1)") (class "Default")
      (node (ref "U$1") (pin "21-A7/RX5/BCLK1") (pinfunction "21-A7/RX5/BCLK1_21-A7/RX5/BCLK1") (pintype "bidirectional"))
    )
    (net (code "253") (name "unconnected-(U$1-Pad22-A8{slash}CTX1)") (class "Default")
      (node (ref "U$1") (pin "22-A8/CTX1") (pinfunction "22-A8/CTX1_22-A8/CTX1") (pintype "bidirectional"))
    )
    (net (code "254") (name "unconnected-(U$1-Pad23-A9{slash}CRX1{slash}MCLK1)") (class "Default")
      (node (ref "U$1") (pin "23-A9/CRX1/MCLK1") (pinfunction "23-A9/CRX1/MCLK1_23-A9/CRX1/MCLK1") (pintype "bidirectional"))
    )
    (net (code "255") (name "unconnected-(U$1-Pad24-A10{slash}TX6{slash}SCL2)") (class "Default")
      (node (ref "U$1") (pin "24-A10/TX6/SCL2") (pinfunction "24-A10/TX6/SCL2_24-A10/TX6/SCL2") (pintype "bidirectional"))
    )
    (net (code "256") (name "unconnected-(U$1-Pad25-A11{slash}RX6{slash}SDA2)") (class "Default")
      (node (ref "U$1") (pin "25-A11/RX6/SDA2") (pinfunction "25-A11/RX6/SDA2_25-A11/RX6/SDA2") (pintype "bidirectional"))
    )
    (net (code "257") (name "unconnected-(U$1-Pad26-A12{slash}MOSI1)") (class "Default")
      (node (ref "U$1") (pin "26-A12/MOSI1") (pinfunction "26-A12/MOSI1_26-A12/MOSI1") (pintype "bidirectional"))
    )
    (net (code "258") (name "unconnected-(U$1-Pad27-A13{slash}SCK1)") (class "Default")
      (node (ref "U$1") (pin "27-A13/SCK1") (pinfunction "27-A13/SCK1_27-A13/SCK1") (pintype "bidirectional"))
    )
    (net (code "259") (name "unconnected-(U$1-Pad28-RX7)") (class "Default")
      (node (ref "U$1") (pin "28-RX7") (pinfunction "28-RX7_28-RX7") (pintype "bidirectional"))
    )
    (net (code "260") (name "unconnected-(U$1-Pad29-TX7)") (class "Default")
      (node (ref "U$1") (pin "29-TX7") (pinfunction "29-TX7_29-TX7") (pintype "bidirectional"))
    )
    (net (code "261") (name "unconnected-(U$1-Pad30-CRX3)") (class "Default")
      (node (ref "U$1") (pin "30-CRX3") (pinfunction "30-CRX3_30-CRX3") (pintype "bidirectional"))
    )
    (net (code "262") (name "unconnected-(U$1-Pad31-CTX3)") (class "Default")
      (node (ref "U$1") (pin "31-CTX3") (pinfunction "31-CTX3_31-CTX3") (pintype "bidirectional"))
    )
    (net (code "263") (name "unconnected-(U$1-Pad32-OUT1B)") (class "Default")
      (node (ref "U$1") (pin "32-OUT1B") (pinfunction "32-OUT1B_32-OUT1B") (pintype "bidirectional"))
    )
    (net (code "264") (name "unconnected-(U$1-Pad33-MCLK2)") (class "Default")
      (node (ref "U$1") (pin "33-MCLK2") (pinfunction "33-MCLK2_33-MCLK2") (pintype "bidirectional"))
    )
    (net (code "265") (name "unconnected-(U$1-Pad34-RX8)") (class "Default")
      (node (ref "U$1") (pin "34-RX8") (pinfunction "34-RX8_34-RX8") (pintype "bidirectional"))
    )
    (net (code "266") (name "unconnected-(U$1-Pad36-PWM)") (class "Default")
      (node (ref "U$1") (pin "36-PWM") (pinfunction "36-PWM_36-PWM") (pintype "bidirectional"))
    )
    (net (code "267") (name "unconnected-(U$1-Pad37-PWM)") (class "Default")
      (node (ref "U$1") (pin "37-PWM") (pinfunction "37-PWM_37-PWM") (pintype "bidirectional"))
    )
    (net (code "268") (name "unconnected-(U$1-Pad38-A14{slash}CS{slash}IN1)") (class "Default")
      (node (ref "U$1") (pin "38-A14/CS/IN1") (pinfunction "38-A14/CS/IN1_38-A14/CS/IN1") (pintype "bidirectional"))
    )
    (net (code "269") (name "unconnected-(U$1-Pad39-A15{slash}CS{slash}OUT1A)") (class "Default")
      (node (ref "U$1") (pin "39-A15/CS/OUT1A") (pinfunction "39-A15/CS/OUT1A_39-A15/CS/OUT1A") (pintype "bidirectional"))
    )
    (net (code "270") (name "unconnected-(U$1-Pad40-A16{slash}CS1)") (class "Default")
      (node (ref "U$1") (pin "40-A16/CS1") (pinfunction "40-A16/CS1_40-A16/CS1") (pintype "bidirectional"))
    )
    (net (code "271") (name "unconnected-(U$1-Pad41-A17{slash}MISO1)") (class "Default")
      (node (ref "U$1") (pin "41-A17/MISO1") (pinfunction "41-A17/MISO1_41-A17/MISO1") (pintype "bidirectional"))
    )
    (net (code "272") (name "unconnected-(U$1-PadD+)") (class "Default")
      (node (ref "U$1") (pin "D+") (pinfunction "D+_D+") (pintype "bidirectional"))
    )
    (net (code "273") (name "unconnected-(U$1-PadD-)") (class "Default")
      (node (ref "U$1") (pin "D-") (pinfunction "D-_D-") (pintype "bidirectional"))
    )
    (net (code "274") (name "unconnected-(U$1-PadDM)") (class "Default")
      (node (ref "U$1") (pin "DM") (pinfunction "DM_DM") (pintype "bidirectional"))
    )
    (net (code "275") (name "unconnected-(U$1-PadDP)") (class "Default")
      (node (ref "U$1") (pin "DP") (pinfunction "DP_DP") (pintype "bidirectional"))
    )
    (net (code "276") (name "unconnected-(U$1-PadG)") (class "Default")
      (node (ref "U$1") (pin "G") (pinfunction "G_G") (pintype "bidirectional"))
    )
    (net (code "277") (name "unconnected-(U$1-PadLED)") (class "Default")
      (node (ref "U$1") (pin "LED") (pinfunction "LED_LED") (pintype "bidirectional"))
    )
    (net (code "278") (name "unconnected-(U$1-PadON{slash}OFF)") (class "Default")
      (node (ref "U$1") (pin "ON/OFF") (pinfunction "ON/OFF_ON/OFF") (pintype "bidirectional"))
    )
    (net (code "279") (name "unconnected-(U$1-PadPROGRAM)") (class "Default")
      (node (ref "U$1") (pin "PROGRAM") (pinfunction "PROGRAM_PROGRAM") (pintype "bidirectional"))
    )
    (net (code "280") (name "unconnected-(U$1-PadR+)") (class "Default")
      (node (ref "U$1") (pin "R+") (pinfunction "R+_R+") (pintype "bidirectional"))
    )
    (net (code "281") (name "unconnected-(U$1-PadR-)") (class "Default")
      (node (ref "U$1") (pin "R-") (pinfunction "R-_R-") (pintype "bidirectional"))
    )
    (net (code "282") (name "unconnected-(U$1-PadT+)") (class "Default")
      (node (ref "U$1") (pin "T+") (pinfunction "T+_T+") (pintype "bidirectional"))
    )
    (net (code "283") (name "unconnected-(U$1-PadT-)") (class "Default")
      (node (ref "U$1") (pin "T-") (pinfunction "T-_T-") (pintype "bidirectional"))
    )
    (net (code "284") (name "unconnected-(U$1-PadVBAT)") (class "Default")
      (node (ref "U$1") (pin "VBAT") (pinfunction "VBAT_VBAT") (pintype "bidirectional"))
    )
    (net (code "285") (name "unconnected-(U$1-PadVIN)") (class "Default")
      (node (ref "U$1") (pin "VIN") (pinfunction "VIN_VIN") (pintype "bidirectional"))
    )
    (net (code "286") (name "unconnected-(U$1-PadVUSB)") (class "Default")
      (node (ref "U$1") (pin "VUSB") (pinfunction "VUSB_VUSB") (pintype "bidirectional"))
    )
    (net (code "287") (name "unconnected-(U$2-PadBOOT)") (class "Default")
      (node (ref "U$2") (pin "BOOT") (pinfunction "BOOT_BOOT") (pintype "bidirectional"))
    )
    (net (code "288") (name "unconnected-(U$2-PadP0)") (class "Default")
      (node (ref "U$2") (pin "P0") (pinfunction "P0_P0") (pintype "bidirectional"))
    )
    (net (code "289") (name "unconnected-(U$2-PadP1)") (class "Default")
      (node (ref "U$2") (pin "P1") (pinfunction "P1_P1") (pintype "bidirectional"))
    )
    (net (code "290") (name "unconnected-(U$2-PadP2)") (class "Default")
      (node (ref "U$2") (pin "P2") (pinfunction "P2_P2") (pintype "bidirectional"))
    )
    (net (code "291") (name "unconnected-(U$2-PadP3)") (class "Default")
      (node (ref "U$2") (pin "P3") (pinfunction "P3_P3") (pintype "bidirectional"))
    )
    (net (code "292") (name "unconnected-(U$2-PadP6)") (class "Default")
      (node (ref "U$2") (pin "P6") (pinfunction "P6_P6") (pintype "bidirectional"))
    )
    (net (code "293") (name "unconnected-(U$2-PadP7)") (class "Default")
      (node (ref "U$2") (pin "P7") (pinfunction "P7_P7") (pintype "bidirectional"))
    )
    (net (code "294") (name "unconnected-(U$2-PadP8)") (class "Default")
      (node (ref "U$2") (pin "P8") (pinfunction "P8_P8") (pintype "bidirectional"))
    )
    (net (code "295") (name "unconnected-(U$2-PadP9)") (class "Default")
      (node (ref "U$2") (pin "P9") (pinfunction "P9_P9") (pintype "bidirectional"))
    )
    (net (code "296") (name "unconnected-(U$2-PadRST)") (class "Default")
      (node (ref "U$2") (pin "RST") (pinfunction "RST_RST") (pintype "bidirectional"))
    )
    (net (code "297") (name "unconnected-(U$2-PadSYNC)") (class "Default")
      (node (ref "U$2") (pin "SYNC") (pinfunction "SYNC_SYNC") (pintype "bidirectional"))
    )
    (net (code "298") (name "unconnected-(U$2-PadVIN)") (class "Default")
      (node (ref "U$2") (pin "VIN") (pinfunction "VIN_VIN") (pintype "bidirectional"))
    )
    (net (code "299") (name "unconnected-(U$3-PadADR)") (class "Default")
      (node (ref "U$3") (pin "ADR") (pinfunction "ADR_ADR") (pintype "bidirectional"))
    )
    (net (code "300") (name "unconnected-(U$3-PadINT)") (class "Default")
      (node (ref "U$3") (pin "INT") (pinfunction "INT_INT") (pintype "bidirectional"))
    )
    (net (code "301") (name "unconnected-(U$3-PadPS0)") (class "Default")
      (node (ref "U$3") (pin "PS0") (pinfunction "PS0_PS0") (pintype "bidirectional"))
    )
    (net (code "302") (name "unconnected-(U$3-PadPS1)") (class "Default")
      (node (ref "U$3") (pin "PS1") (pinfunction "PS1_PS1") (pintype "bidirectional"))
    )
    (net (code "303") (name "unconnected-(U$3-PadRST)") (class "Default")
      (node (ref "U$3") (pin "RST") (pinfunction "RST_RST") (pintype "bidirectional"))
    )
    (net (code "304") (name "unconnected-(U$3-PadVIN)") (class "Default")
      (node (ref "U$3") (pin "VIN") (pinfunction "VIN_VIN") (pintype "bidirectional"))
    )
  )
)
